# FMC_P_CAM.net
KiCad netlist of a schematic drawn in EAGLE
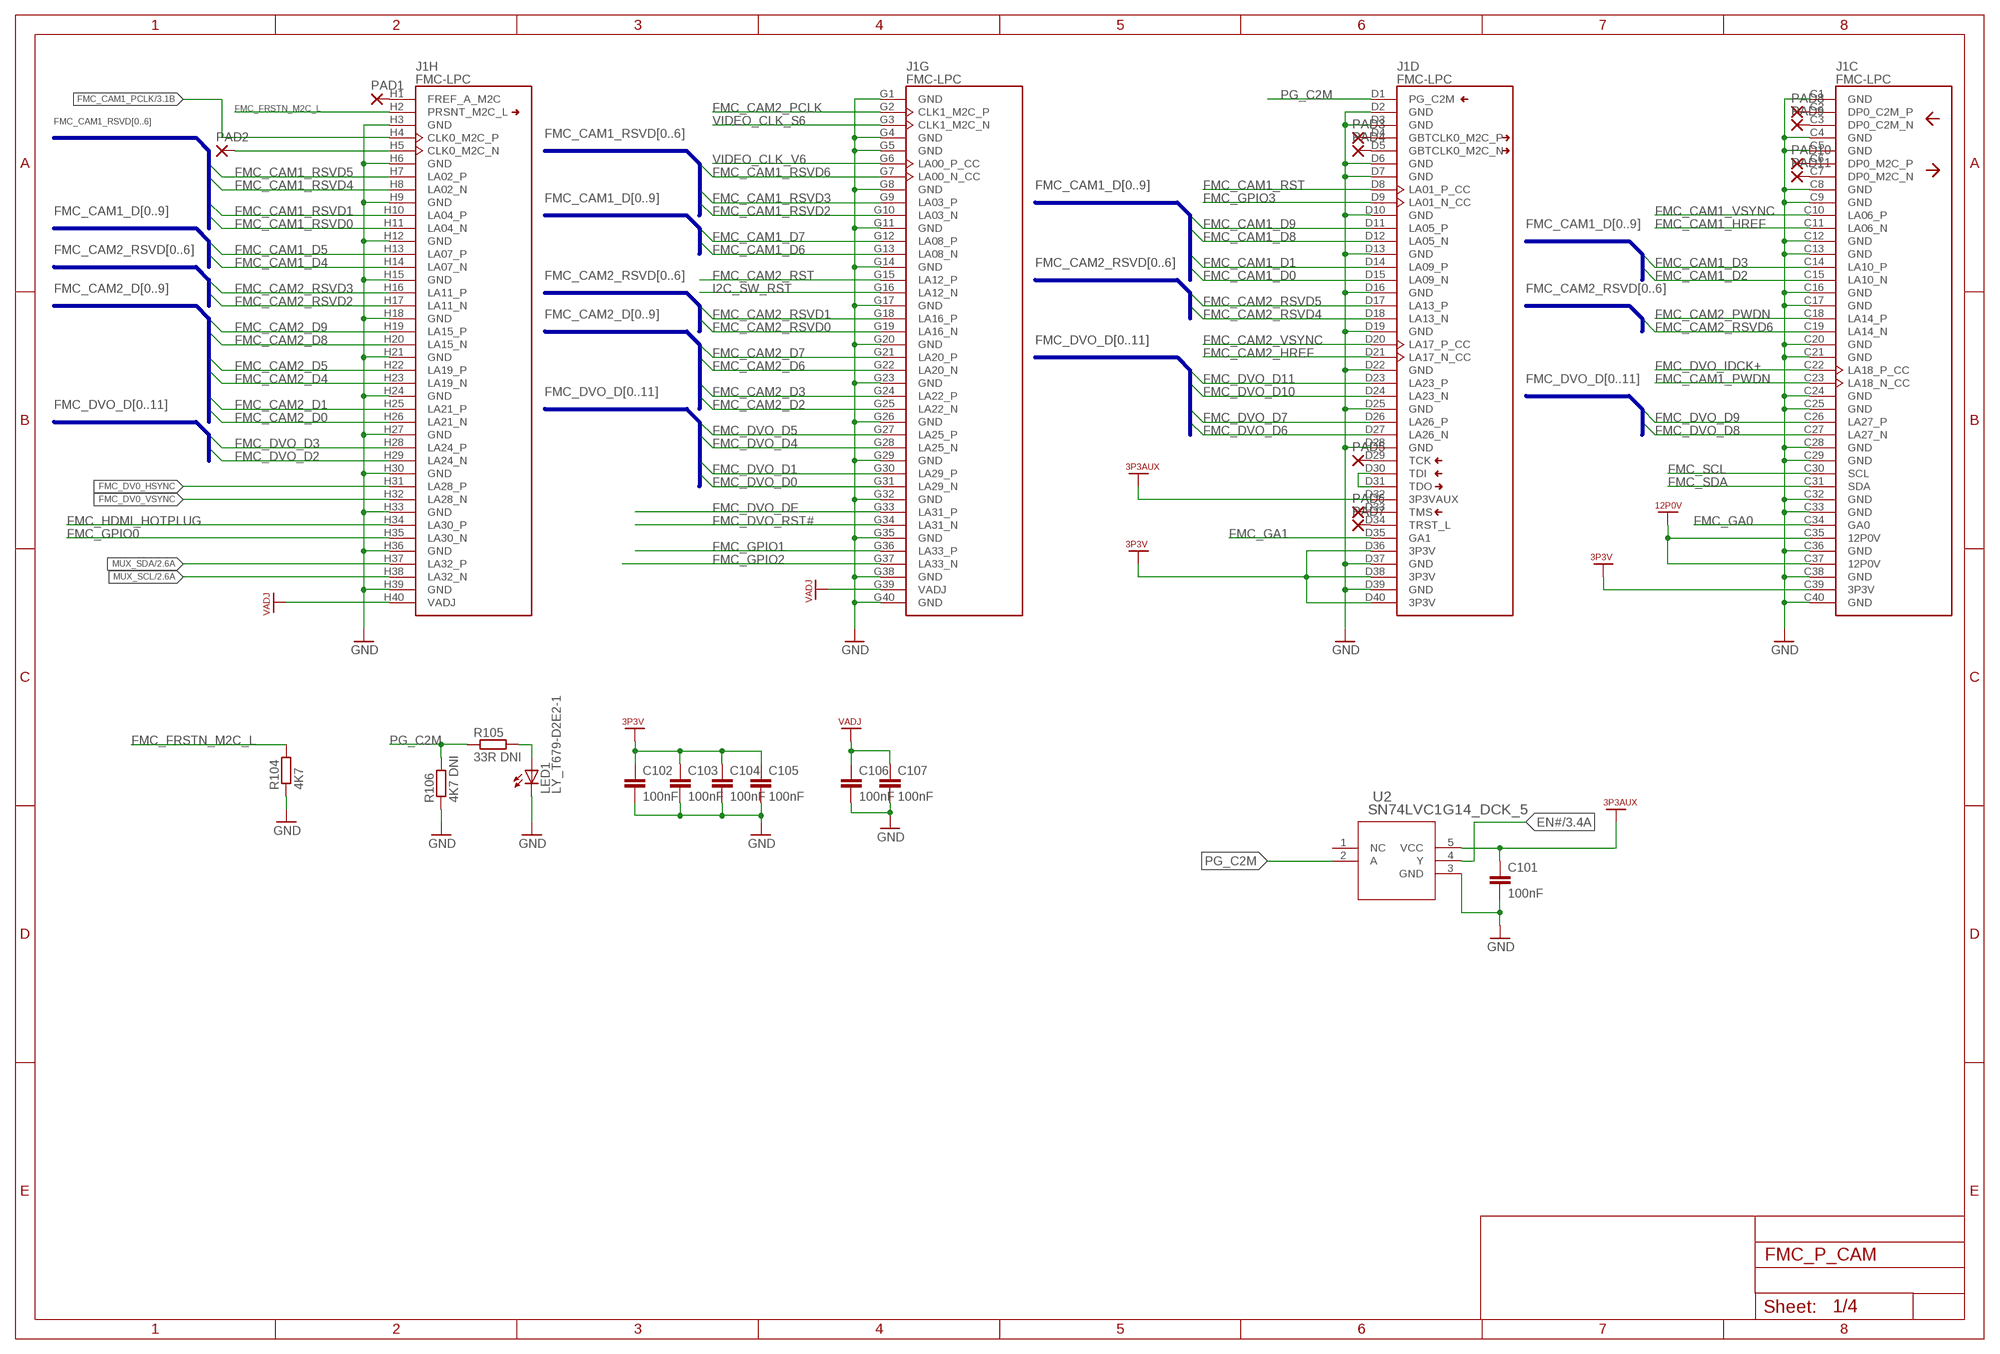
[diagram p0: schematic, sheet 1]
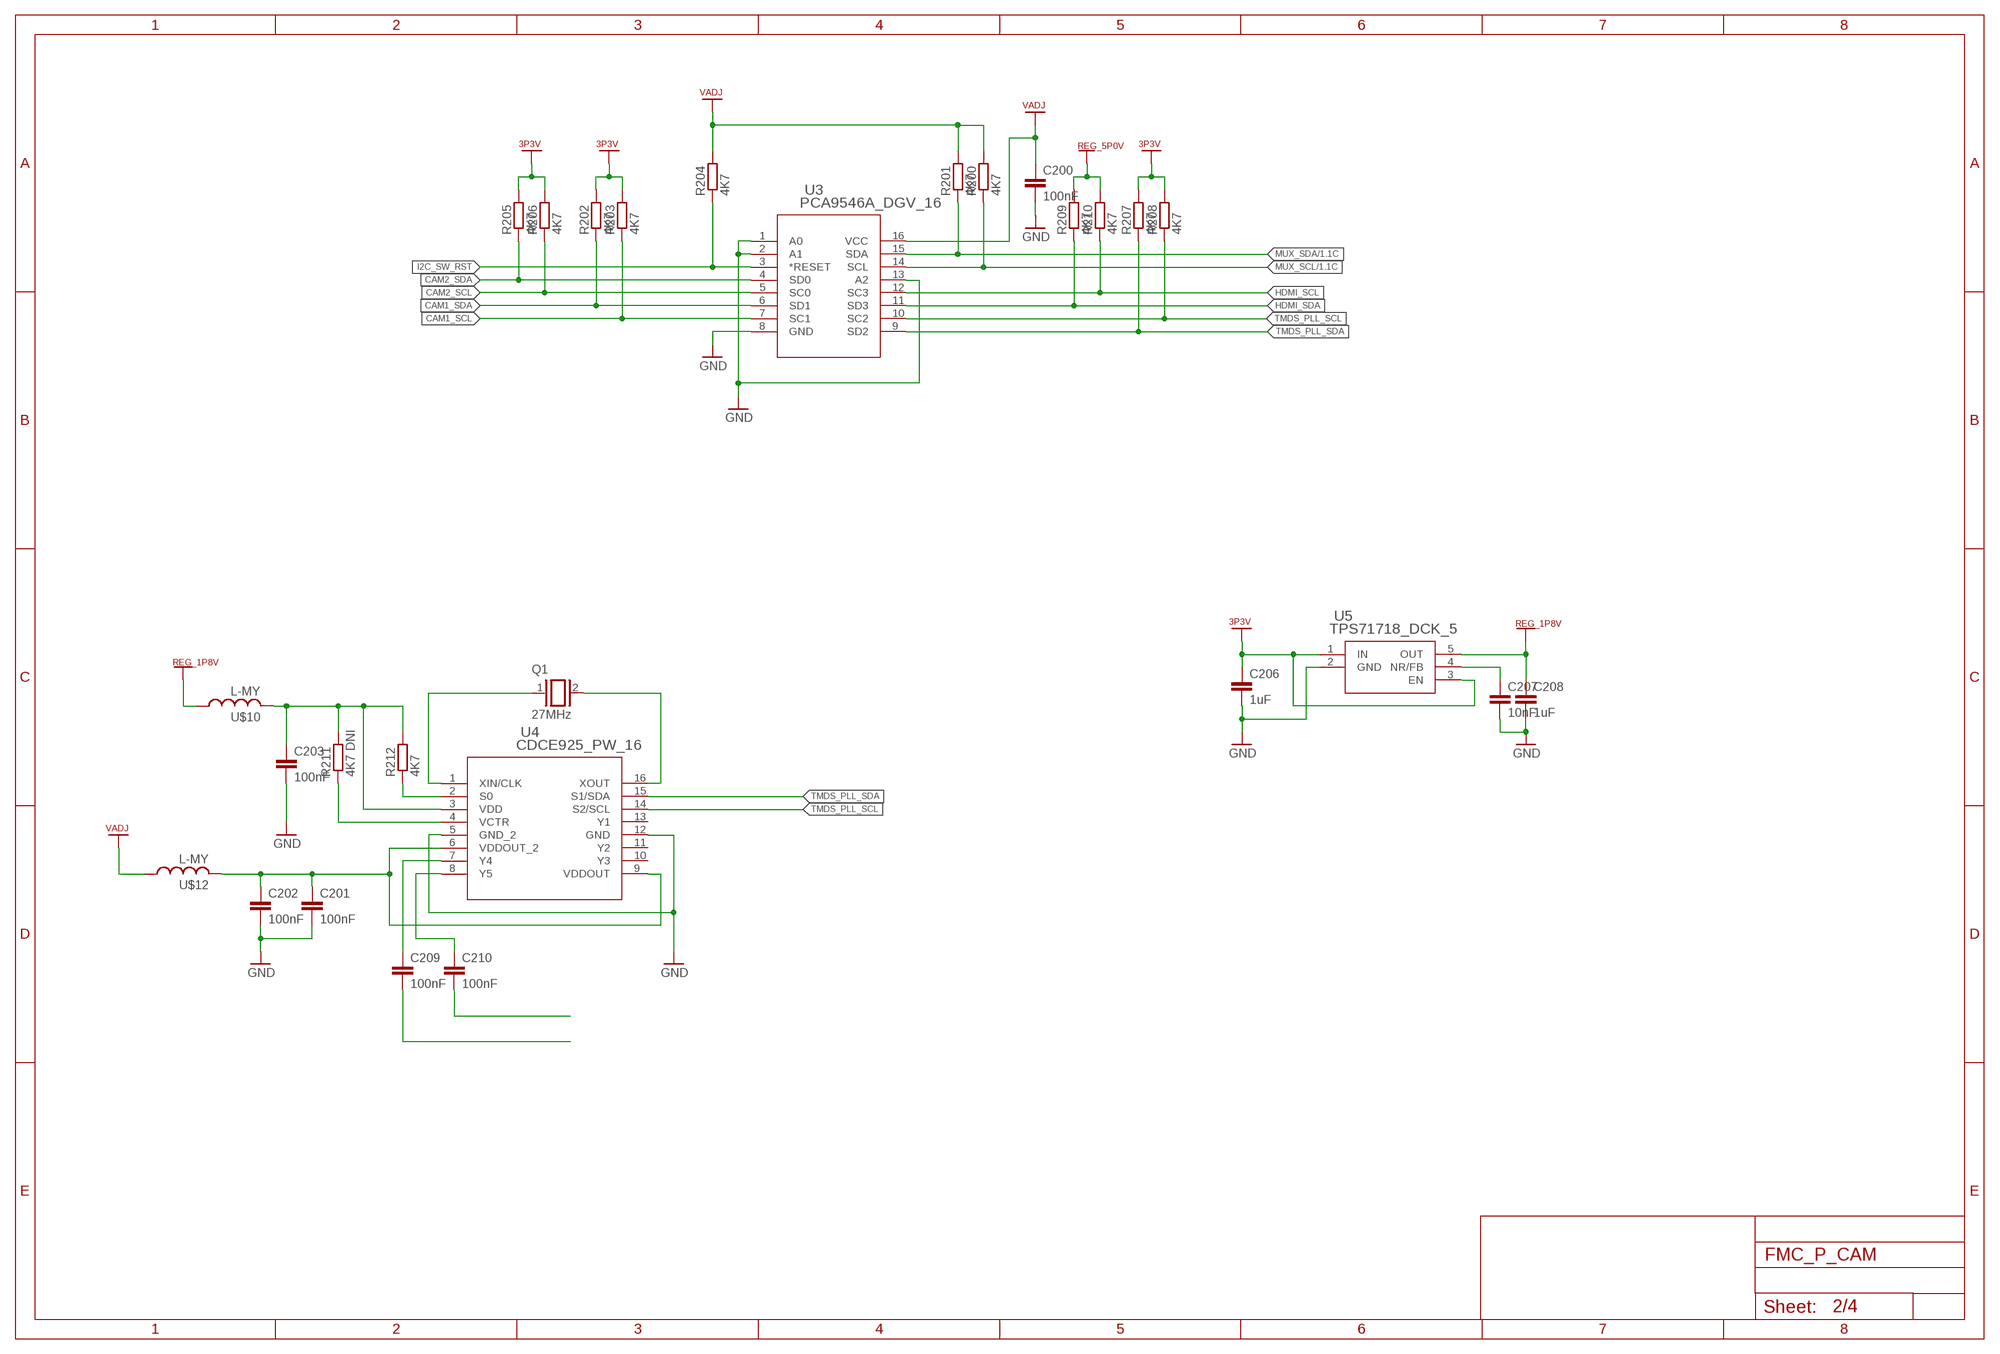
[diagram p1: schematic, sheet 2]
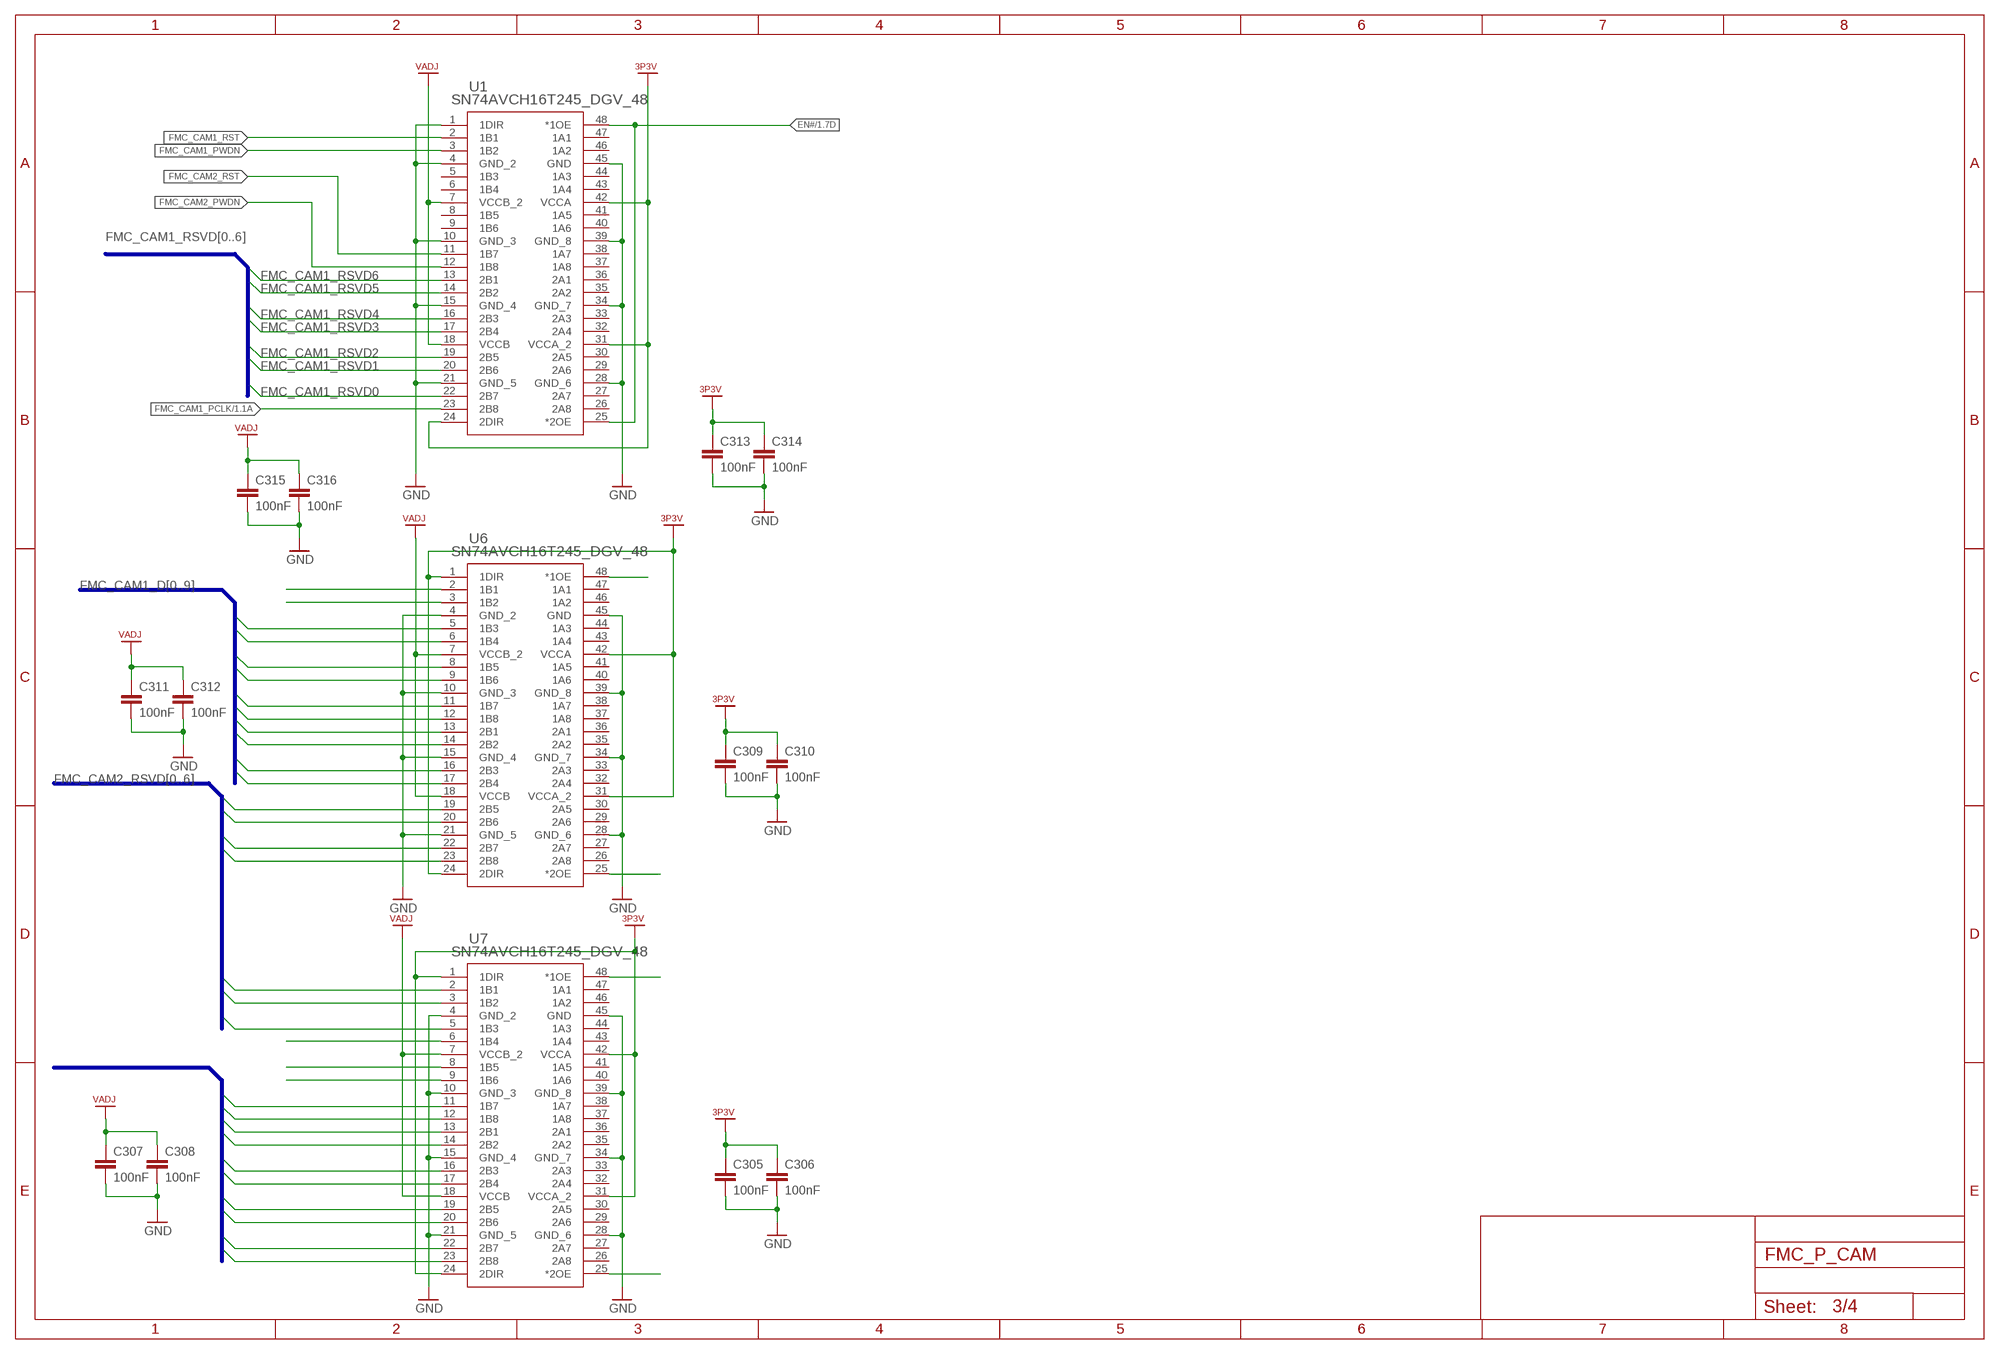
[diagram p2: schematic, sheet 3]
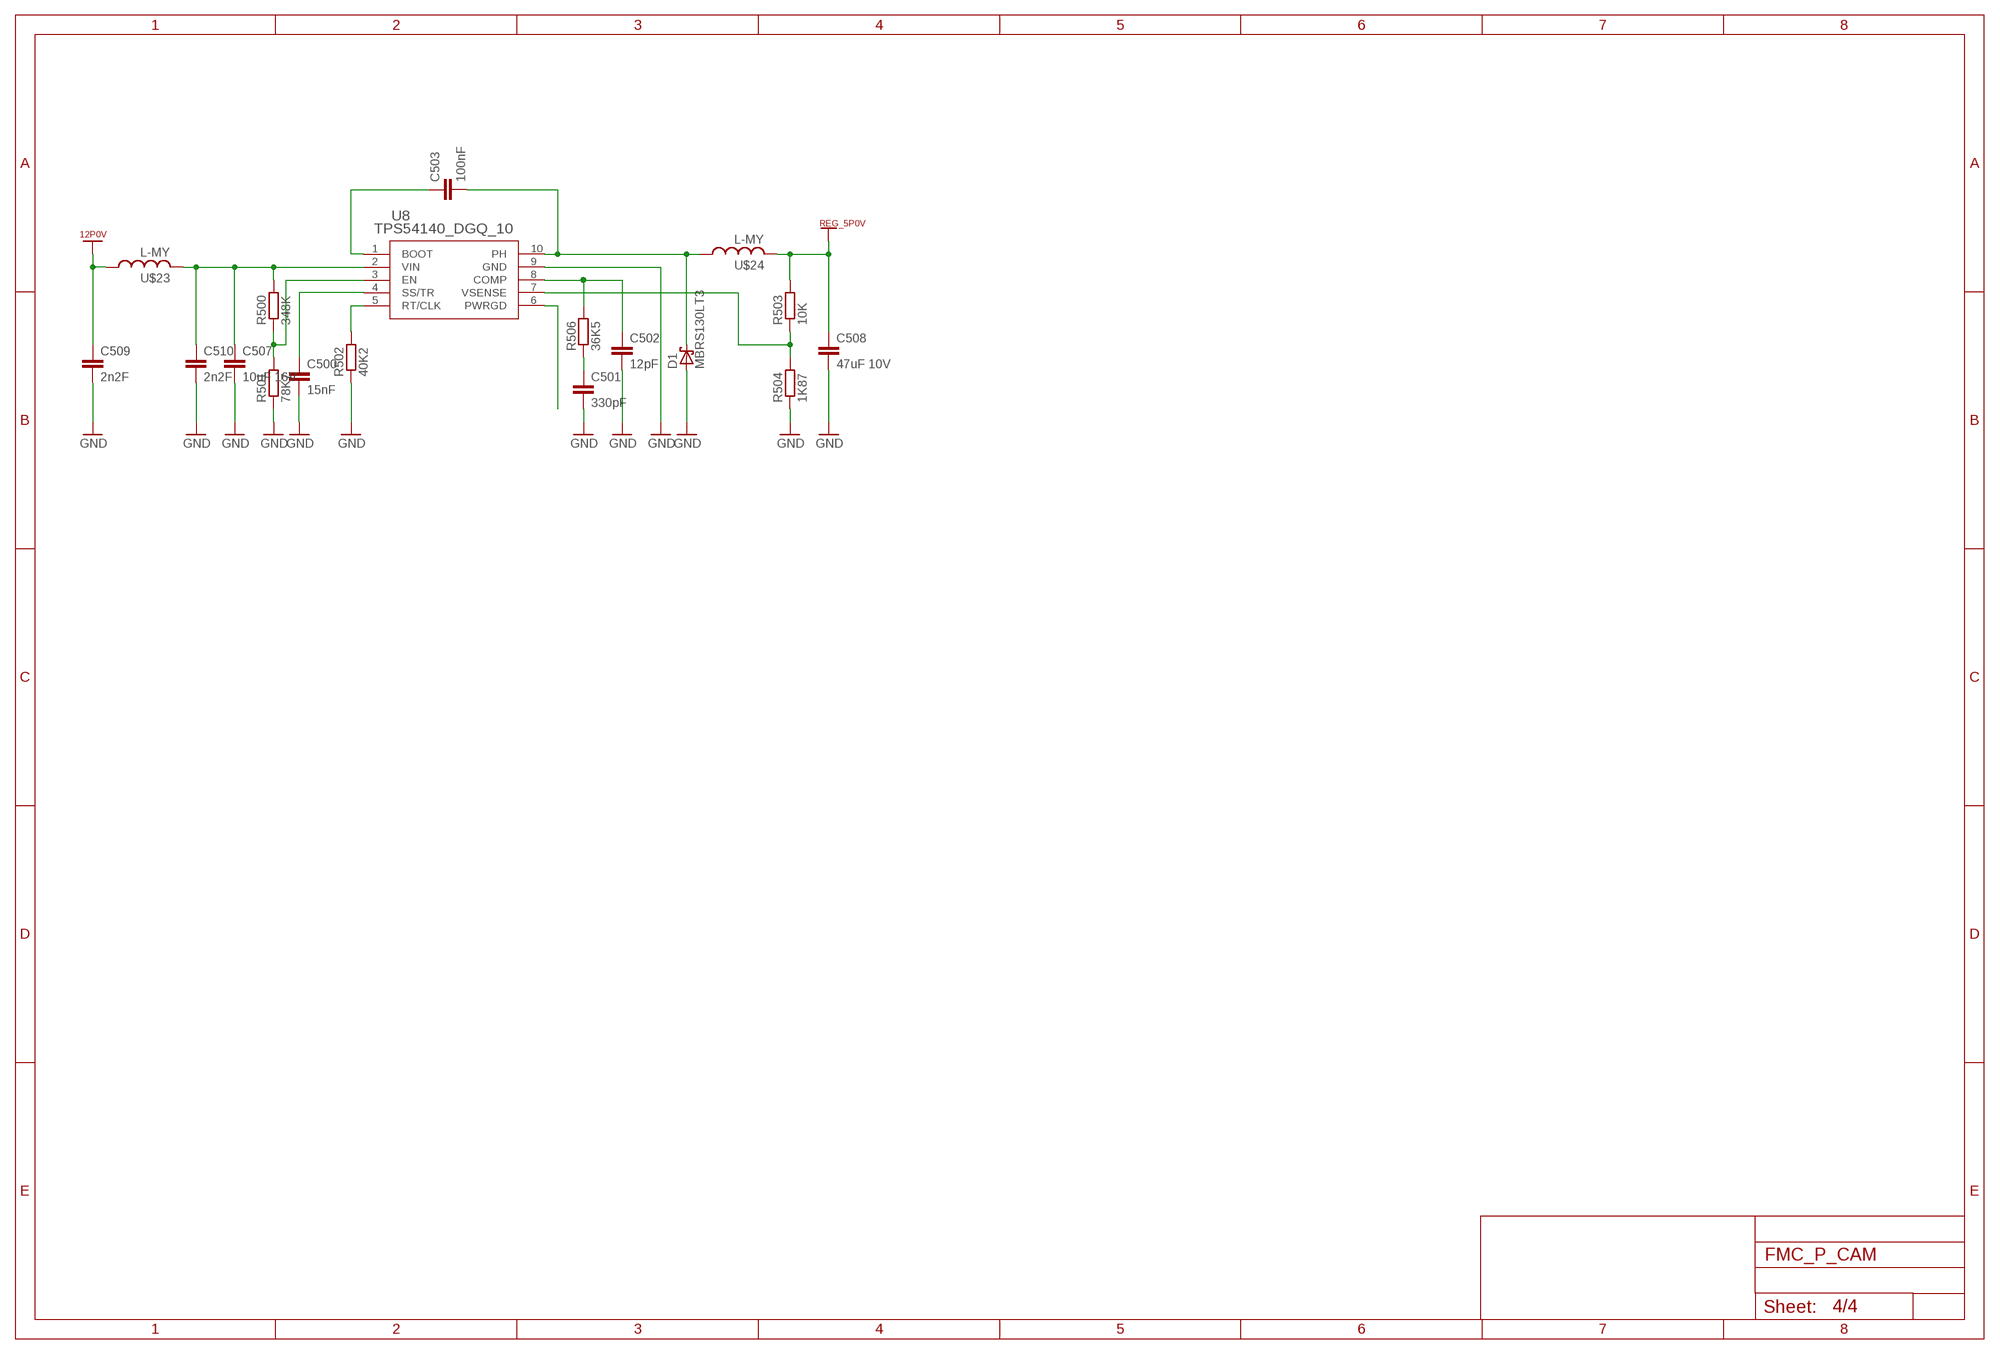
[diagram p3: schematic, sheet 4]

(export (version "E")
  (design (tool "Eeschema 10.0.6"))
  (components
    (comp (ref "C305")
      (value "100nF")
      (footprint "eagle-import:C0603")
      (libsource (lib "eagle-import") (part "rcl_C-EUC0603"))
    )
    (comp (ref "C306")
      (value "100nF")
      (footprint "eagle-import:C0603")
      (libsource (lib "eagle-import") (part "rcl_C-EUC0603"))
    )
    (comp (ref "C307")
      (value "100nF")
      (footprint "eagle-import:C0603")
      (libsource (lib "eagle-import") (part "rcl_C-EUC0603"))
    )
    (comp (ref "C308")
      (value "100nF")
      (footprint "eagle-import:C0603")
      (libsource (lib "eagle-import") (part "rcl_C-EUC0603"))
    )
    (comp (ref "C309")
      (value "100nF")
      (footprint "eagle-import:C0603")
      (libsource (lib "eagle-import") (part "rcl_C-EUC0603"))
    )
    (comp (ref "C310")
      (value "100nF")
      (footprint "eagle-import:C0603")
      (libsource (lib "eagle-import") (part "rcl_C-EUC0603"))
    )
    (comp (ref "C311")
      (value "100nF")
      (footprint "eagle-import:C0603")
      (libsource (lib "eagle-import") (part "rcl_C-EUC0603"))
    )
    (comp (ref "C312")
      (value "100nF")
      (footprint "eagle-import:C0603")
      (libsource (lib "eagle-import") (part "rcl_C-EUC0603"))
    )
    (comp (ref "C313")
      (value "100nF")
      (footprint "eagle-import:C0603")
      (libsource (lib "eagle-import") (part "rcl_C-EUC0603"))
    )
    (comp (ref "C314")
      (value "100nF")
      (footprint "eagle-import:C0603")
      (libsource (lib "eagle-import") (part "rcl_C-EUC0603"))
    )
    (comp (ref "C315")
      (value "100nF")
      (footprint "eagle-import:C0603")
      (libsource (lib "eagle-import") (part "rcl_C-EUC0603"))
    )
    (comp (ref "C316")
      (value "100nF")
      (footprint "eagle-import:C0603")
      (libsource (lib "eagle-import") (part "rcl_C-EUC0603"))
    )
    (comp (ref "U1")
      (value "SN74AVCH16T245_DGV_48")
      (footprint "eagle-import:DGV48")
      (fields
        (field (name "GENERIC_PART_NUMBER") "SN74AVCH16T245")
        (field (name "MANUFACTURER") "Texas Instruments")
        (field (name "MANUFACTURER_PART_NUMBER") "sn74avch16t245_dgv_48")
      )
      (libsource (lib "eagle-import") (part "SN74AVCH16T245_DGV_48"))
    )
    (comp (ref "U6")
      (value "SN74AVCH16T245_DGV_48")
      (footprint "eagle-import:DGV48")
      (fields
        (field (name "GENERIC_PART_NUMBER") "SN74AVCH16T245")
        (field (name "MANUFACTURER") "Texas Instruments")
        (field (name "MANUFACTURER_PART_NUMBER") "sn74avch16t245_dgv_48")
      )
      (libsource (lib "eagle-import") (part "SN74AVCH16T245_DGV_48"))
    )
    (comp (ref "U7")
      (value "SN74AVCH16T245_DGV_48")
      (footprint "eagle-import:DGV48")
      (fields
        (field (name "GENERIC_PART_NUMBER") "SN74AVCH16T245")
        (field (name "MANUFACTURER") "Texas Instruments")
        (field (name "MANUFACTURER_PART_NUMBER") "sn74avch16t245_dgv_48")
      )
      (libsource (lib "eagle-import") (part "SN74AVCH16T245_DGV_48"))
    )
    (comp (ref "C500")
      (value "15nF")
      (footprint "eagle-import:C0603")
      (libsource (lib "eagle-import") (part "rcl_C-EUC0603"))
    )
    (comp (ref "C501")
      (value "330pF")
      (footprint "eagle-import:C0603")
      (libsource (lib "eagle-import") (part "rcl_C-EUC0603"))
    )
    (comp (ref "C502")
      (value "12pF")
      (footprint "eagle-import:C0603")
      (libsource (lib "eagle-import") (part "rcl_C-EUC0603"))
    )
    (comp (ref "C503")
      (value "100nF")
      (footprint "eagle-import:C0603")
      (libsource (lib "eagle-import") (part "rcl_C-EUC0603"))
    )
    (comp (ref "C507")
      (value "10uF 16V")
      (footprint "eagle-import:C0603")
      (libsource (lib "eagle-import") (part "rcl_C-EUC0603"))
    )
    (comp (ref "C508")
      (value "47uF 10V")
      (footprint "eagle-import:C0603")
      (libsource (lib "eagle-import") (part "rcl_C-EUC0603"))
    )
    (comp (ref "C509")
      (value "2n2F")
      (footprint "eagle-import:C0603")
      (libsource (lib "eagle-import") (part "rcl_C-EUC0603"))
    )
    (comp (ref "C510")
      (value "2n2F")
      (footprint "eagle-import:C0603")
      (libsource (lib "eagle-import") (part "rcl_C-EUC0603"))
    )
    (comp (ref "D1")
      (value "MBRS130LT3")
      (footprint "eagle-import:SMB")
      (libsource (lib "eagle-import") (part "MBRS130LT3"))
    )
    (comp (ref "R500")
      (value "348K")
      (footprint "eagle-import:R0603")
      (libsource (lib "eagle-import") (part "R-EU_R0603"))
    )
    (comp (ref "R501")
      (value "78K7")
      (footprint "eagle-import:R0603")
      (libsource (lib "eagle-import") (part "R-EU_R0603"))
    )
    (comp (ref "R502")
      (value "40K2")
      (footprint "eagle-import:R0603")
      (libsource (lib "eagle-import") (part "R-EU_R0603"))
    )
    (comp (ref "R503")
      (value "10K")
      (footprint "eagle-import:R0603")
      (libsource (lib "eagle-import") (part "R-EU_R0603"))
    )
    (comp (ref "R504")
      (value "1K87")
      (footprint "eagle-import:R0603")
      (libsource (lib "eagle-import") (part "R-EU_R0603"))
    )
    (comp (ref "R506")
      (value "36K5")
      (footprint "eagle-import:R0603")
      (libsource (lib "eagle-import") (part "R-EU_R0603"))
    )
    (comp (ref "U$23")
      (value "L-MY")
      (footprint "eagle-import:R0603")
      (libsource (lib "eagle-import") (part "L-MY"))
    )
    (comp (ref "U$24")
      (value "L-MY")
      (footprint "eagle-import:R0603")
      (libsource (lib "eagle-import") (part "L-MY"))
    )
    (comp (ref "U8")
      (value "TPS54140_DGQ_10")
      (footprint "eagle-import:DGQ10_1P88X1P57")
      (fields
        (field (name "GENERIC_PART_NUMBER") "TPS54140")
        (field (name "MANUFACTURER") "Texas Instruments")
        (field (name "MANUFACTURER_PART_NUMBER") "tps54140_dgq_10")
      )
      (libsource (lib "eagle-import") (part "TPS54140_DGQ_10"))
    )
    (comp (ref "C101")
      (value "100nF")
      (footprint "eagle-import:C0603")
      (libsource (lib "eagle-import") (part "resistor_C-EUC0603"))
    )
    (comp (ref "C102")
      (value "100nF")
      (footprint "eagle-import:C0603")
      (libsource (lib "eagle-import") (part "resistor_C-EUC0603"))
    )
    (comp (ref "C103")
      (value "100nF")
      (footprint "eagle-import:C0603")
      (libsource (lib "eagle-import") (part "resistor_C-EUC0603"))
    )
    (comp (ref "C104")
      (value "100nF")
      (footprint "eagle-import:C0603")
      (libsource (lib "eagle-import") (part "resistor_C-EUC0603"))
    )
    (comp (ref "C105")
      (value "100nF")
      (footprint "eagle-import:C0603")
      (libsource (lib "eagle-import") (part "resistor_C-EUC0603"))
    )
    (comp (ref "C106")
      (value "100nF")
      (footprint "eagle-import:C0603")
      (libsource (lib "eagle-import") (part "resistor_C-EUC0603"))
    )
    (comp (ref "C107")
      (value "100nF")
      (footprint "eagle-import:C0603")
      (libsource (lib "eagle-import") (part "resistor_C-EUC0603"))
    )
    (comp (ref "J1")
      (value "FMC-LPC")
      (footprint "eagle-import:FMC-LPC-MALE")
      (fields (field (name "OC_NEWARK") "unknown"))
      (libsource (lib "eagle-import") (part "FMC-LPC"))
    )
    (comp (ref "LED1")
      (value "LY_T679-D2E2-1")
      (footprint "eagle-import:PLCC2")
      (libsource (lib "eagle-import") (part "_T679-?-1D2E2LY"))
    )
    (comp (ref "PAD1")
      (value "1,6/0,8")
      (footprint "eagle-import:1,6_0,8")
      (libsource (lib "eagle-import") (part "1,6/0,8"))
    )
    (comp (ref "PAD2")
      (value "1,6/0,8")
      (footprint "eagle-import:1,6_0,8")
      (libsource (lib "eagle-import") (part "1,6/0,8"))
    )
    (comp (ref "PAD3")
      (value "1,6/0,8")
      (footprint "eagle-import:1,6_0,8")
      (libsource (lib "eagle-import") (part "1,6/0,8"))
    )
    (comp (ref "PAD4")
      (value "1,6/0,8")
      (footprint "eagle-import:1,6_0,8")
      (libsource (lib "eagle-import") (part "1,6/0,8"))
    )
    (comp (ref "PAD5")
      (value "1,6/0,8")
      (footprint "eagle-import:1,6_0,8")
      (libsource (lib "eagle-import") (part "1,6/0,8"))
    )
    (comp (ref "PAD6")
      (value "1,6/0,8")
      (footprint "eagle-import:1,6_0,8")
      (libsource (lib "eagle-import") (part "1,6/0,8"))
    )
    (comp (ref "PAD7")
      (value "1,6/0,8")
      (footprint "eagle-import:1,6_0,8")
      (libsource (lib "eagle-import") (part "1,6/0,8"))
    )
    (comp (ref "PAD8")
      (value "1,6/0,8")
      (footprint "eagle-import:1,6_0,8")
      (libsource (lib "eagle-import") (part "1,6/0,8"))
    )
    (comp (ref "PAD9")
      (value "1,6/0,8")
      (footprint "eagle-import:1,6_0,8")
      (libsource (lib "eagle-import") (part "1,6/0,8"))
    )
    (comp (ref "PAD10")
      (value "1,6/0,8")
      (footprint "eagle-import:1,6_0,8")
      (libsource (lib "eagle-import") (part "1,6/0,8"))
    )
    (comp (ref "PAD11")
      (value "1,6/0,8")
      (footprint "eagle-import:1,6_0,8")
      (libsource (lib "eagle-import") (part "1,6/0,8"))
    )
    (comp (ref "R104")
      (value "4K7")
      (footprint "eagle-import:R0603")
      (libsource (lib "eagle-import") (part "resistor_R-EU_R0603"))
    )
    (comp (ref "R105")
      (value "33R DNI")
      (footprint "eagle-import:R0603")
      (libsource (lib "eagle-import") (part "resistor_R-EU_R0603"))
    )
    (comp (ref "R106")
      (value "4K7 DNI")
      (footprint "eagle-import:R0603")
      (libsource (lib "eagle-import") (part "resistor_R-EU_R0603"))
    )
    (comp (ref "U2")
      (value "SN74LVC1G14_DCK_5")
      (footprint "eagle-import:DCK5")
      (fields
        (field (name "GENERIC_PART_NUMBER") "SN74LVC1G14")
        (field (name "MANUFACTURER") "Texas Instruments")
        (field (name "MANUFACTURER_PART_NUMBER") "sn74lvc1g14_dck_5")
      )
      (libsource (lib "eagle-import") (part "SN74LVC1G14_DCK_5"))
    )
    (comp (ref "C200")
      (value "100nF")
      (footprint "eagle-import:C0603")
      (libsource (lib "eagle-import") (part "C-EUC0603"))
    )
    (comp (ref "C201")
      (value "100nF")
      (footprint "eagle-import:C0603")
      (libsource (lib "eagle-import") (part "C-EUC0603"))
    )
    (comp (ref "C202")
      (value "100nF")
      (footprint "eagle-import:C0603")
      (libsource (lib "eagle-import") (part "C-EUC0603"))
    )
    (comp (ref "C203")
      (value "100nF")
      (footprint "eagle-import:C0603")
      (libsource (lib "eagle-import") (part "C-EUC0603"))
    )
    (comp (ref "C206")
      (value "1uF")
      (footprint "eagle-import:C0603")
      (libsource (lib "eagle-import") (part "C-EUC0603"))
    )
    (comp (ref "C207")
      (value "10nF")
      (footprint "eagle-import:C0603")
      (libsource (lib "eagle-import") (part "C-EUC0603"))
    )
    (comp (ref "C208")
      (value "1uF")
      (footprint "eagle-import:C0603")
      (libsource (lib "eagle-import") (part "C-EUC0603"))
    )
    (comp (ref "C209")
      (value "100nF")
      (footprint "eagle-import:C0603")
      (libsource (lib "eagle-import") (part "C-EUC0603"))
    )
    (comp (ref "C210")
      (value "100nF")
      (footprint "eagle-import:C0603")
      (libsource (lib "eagle-import") (part "C-EUC0603"))
    )
    (comp (ref "Q1")
      (value "27MHz")
      (footprint "eagle-import:Q")
      (libsource (lib "eagle-import") (part "XTAL"))
    )
    (comp (ref "R200")
      (value "4K7")
      (footprint "eagle-import:R0603")
      (libsource (lib "eagle-import") (part "resistor_R-EU_R0603"))
    )
    (comp (ref "R201")
      (value "4K7")
      (footprint "eagle-import:R0603")
      (libsource (lib "eagle-import") (part "resistor_R-EU_R0603"))
    )
    (comp (ref "R202")
      (value "4K7")
      (footprint "eagle-import:R0603")
      (libsource (lib "eagle-import") (part "resistor_R-EU_R0603"))
    )
    (comp (ref "R203")
      (value "4K7")
      (footprint "eagle-import:R0603")
      (libsource (lib "eagle-import") (part "resistor_R-EU_R0603"))
    )
    (comp (ref "R204")
      (value "4K7")
      (footprint "eagle-import:R0603")
      (libsource (lib "eagle-import") (part "resistor_R-EU_R0603"))
    )
    (comp (ref "R205")
      (value "4K7")
      (footprint "eagle-import:R0603")
      (libsource (lib "eagle-import") (part "resistor_R-EU_R0603"))
    )
    (comp (ref "R206")
      (value "4K7")
      (footprint "eagle-import:R0603")
      (libsource (lib "eagle-import") (part "resistor_R-EU_R0603"))
    )
    (comp (ref "R207")
      (value "4K7")
      (footprint "eagle-import:R0603")
      (libsource (lib "eagle-import") (part "resistor_R-EU_R0603"))
    )
    (comp (ref "R208")
      (value "4K7")
      (footprint "eagle-import:R0603")
      (libsource (lib "eagle-import") (part "resistor_R-EU_R0603"))
    )
    (comp (ref "R209")
      (value "4K7")
      (footprint "eagle-import:R0603")
      (libsource (lib "eagle-import") (part "resistor_R-EU_R0603"))
    )
    (comp (ref "R210")
      (value "4K7")
      (footprint "eagle-import:R0603")
      (libsource (lib "eagle-import") (part "resistor_R-EU_R0603"))
    )
    (comp (ref "R211")
      (value "4K7 DNI")
      (footprint "eagle-import:R0603")
      (libsource (lib "eagle-import") (part "resistor_R-EU_R0603"))
    )
    (comp (ref "R212")
      (value "4K7")
      (footprint "eagle-import:R0603")
      (libsource (lib "eagle-import") (part "resistor_R-EU_R0603"))
    )
    (comp (ref "U$10")
      (value "L-MY")
      (footprint "eagle-import:R0603")
      (libsource (lib "eagle-import") (part "L-MY"))
    )
    (comp (ref "U$12")
      (value "L-MY")
      (footprint "eagle-import:R0603")
      (libsource (lib "eagle-import") (part "L-MY"))
    )
    (comp (ref "U3")
      (value "PCA9546A_DGV_16")
      (footprint "eagle-import:DGV16")
      (fields
        (field (name "GENERIC_PART_NUMBER") "PCA9546A")
        (field (name "MANUFACTURER") "Texas Instruments")
        (field (name "MANUFACTURER_PART_NUMBER") "pca9546a_dgv_16")
      )
      (libsource (lib "eagle-import") (part "PCA9546A_DGV_16"))
    )
    (comp (ref "U4")
      (value "CDCE925_PW_16")
      (footprint "eagle-import:PW16")
      (fields
        (field (name "GENERIC_PART_NUMBER") "CDCE925")
        (field (name "MANUFACTURER") "Texas Instruments")
      )
      (libsource (lib "eagle-import") (part "CDCE925_PW_16"))
    )
    (comp (ref "U5")
      (value "TPS71718_DCK_5")
      (footprint "eagle-import:DCK5")
      (fields
        (field (name "GENERIC_PART_NUMBER") "TPS71718")
        (field (name "MANUFACTURER") "Texas Instruments")
        (field (name "MANUFACTURER_PART_NUMBER") "tps71718_dck_5")
      )
      (libsource (lib "eagle-import") (part "TPS71718_DCK_5"))
    )
  )
  (nets
    (net (code "9") (name "3P3AUX") (class "Default")
      (node (ref "C101") (pin "1") (pinfunction "1_1") (pintype "passive"))
      (node (ref "J1") (pin "D32") (pinfunction "3P3VAUX_D32") (pintype "passive"))
      (node (ref "U2") (pin "5") (pinfunction "VCC_5") (pintype "power_in"))
    )
    (net (code "10") (name "3P3V") (class "Default")
      (node (ref "C102") (pin "1") (pinfunction "1_1") (pintype "passive"))
      (node (ref "C103") (pin "1") (pinfunction "1_1") (pintype "passive"))
      (node (ref "C104") (pin "1") (pinfunction "1_1") (pintype "passive"))
      (node (ref "C105") (pin "1") (pinfunction "1_1") (pintype "passive"))
      (node (ref "C206") (pin "1") (pinfunction "1_1") (pintype "passive"))
      (node (ref "C305") (pin "1") (pinfunction "1_1") (pintype "passive"))
      (node (ref "C306") (pin "1") (pinfunction "1_1") (pintype "passive"))
      (node (ref "C309") (pin "1") (pinfunction "1_1") (pintype "passive"))
      (node (ref "C310") (pin "1") (pinfunction "1_1") (pintype "passive"))
      (node (ref "C313") (pin "1") (pinfunction "1_1") (pintype "passive"))
      (node (ref "C314") (pin "1") (pinfunction "1_1") (pintype "passive"))
      (node (ref "J1") (pin "C39") (pinfunction "3P3V_C39") (pintype "passive"))
      (node (ref "J1") (pin "D36") (pinfunction "3P3V_D36") (pintype "passive"))
      (node (ref "J1") (pin "D38") (pinfunction "3P3V_D38") (pintype "passive"))
      (node (ref "J1") (pin "D40") (pinfunction "3P3V_D40") (pintype "passive"))
      (node (ref "R202") (pin "2") (pinfunction "2_2") (pintype "passive"))
      (node (ref "R203") (pin "2") (pinfunction "2_2") (pintype "passive"))
      (node (ref "R205") (pin "2") (pinfunction "2_2") (pintype "passive"))
      (node (ref "R206") (pin "2") (pinfunction "2_2") (pintype "passive"))
      (node (ref "R207") (pin "2") (pinfunction "2_2") (pintype "passive"))
      (node (ref "R208") (pin "2") (pinfunction "2_2") (pintype "passive"))
      (node (ref "U1") (pin "24") (pinfunction "2DIR_24") (pintype "input"))
      (node (ref "U1") (pin "31") (pinfunction "VCCA_2_31") (pintype "power_in"))
      (node (ref "U1") (pin "42") (pinfunction "VCCA_42") (pintype "power_in"))
      (node (ref "U5") (pin "1") (pinfunction "IN_1") (pintype "input"))
      (node (ref "U5") (pin "3") (pinfunction "EN_3") (pintype "passive"))
      (node (ref "U6") (pin "1") (pinfunction "1DIR_1") (pintype "input"))
      (node (ref "U6") (pin "24") (pinfunction "2DIR_24") (pintype "input"))
      (node (ref "U6") (pin "31") (pinfunction "VCCA_2_31") (pintype "power_in"))
      (node (ref "U6") (pin "42") (pinfunction "VCCA_42") (pintype "power_in"))
      (node (ref "U7") (pin "1") (pinfunction "1DIR_1") (pintype "input"))
      (node (ref "U7") (pin "24") (pinfunction "2DIR_24") (pintype "input"))
      (node (ref "U7") (pin "31") (pinfunction "VCCA_2_31") (pintype "power_in"))
      (node (ref "U7") (pin "42") (pinfunction "VCCA_42") (pintype "power_in"))
    )
    (net (code "11") (name "12P0V") (class "Default")
      (node (ref "C509") (pin "1") (pinfunction "1_1") (pintype "passive"))
      (node (ref "J1") (pin "C35") (pinfunction "12P0V_C35") (pintype "passive"))
      (node (ref "J1") (pin "C37") (pinfunction "12P0V_C37") (pintype "passive"))
      (node (ref "U$23") (pin "1") (pinfunction "1_1") (pintype "passive"))
    )
    (net (code "12") (name "CAM1_SCL") (class "Default")
      (node (ref "R203") (pin "1") (pinfunction "1_1") (pintype "passive"))
      (node (ref "U3") (pin "7") (pinfunction "SC1_7") (pintype "passive"))
    )
    (net (code "13") (name "CAM1_SDA") (class "Default")
      (node (ref "R202") (pin "1") (pinfunction "1_1") (pintype "passive"))
      (node (ref "U3") (pin "6") (pinfunction "SD1_6") (pintype "passive"))
    )
    (net (code "14") (name "CAM2_SCL") (class "Default")
      (node (ref "R206") (pin "1") (pinfunction "1_1") (pintype "passive"))
      (node (ref "U3") (pin "5") (pinfunction "SC0_5") (pintype "passive"))
    )
    (net (code "15") (name "CAM2_SDA") (class "Default")
      (node (ref "R205") (pin "1") (pinfunction "1_1") (pintype "passive"))
      (node (ref "U3") (pin "4") (pinfunction "SD0_4") (pintype "passive"))
    )
    (net (code "16") (name "EN#") (class "Default")
      (node (ref "U1") (pin "25") (pinfunction "*2OE_25") (pintype "input"))
      (node (ref "U1") (pin "48") (pinfunction "*1OE_48") (pintype "input"))
      (node (ref "U2") (pin "4") (pinfunction "Y_4") (pintype "output"))
      (node (ref "U6") (pin "25") (pinfunction "*2OE_25") (pintype "input"))
      (node (ref "U6") (pin "48") (pinfunction "*1OE_48") (pintype "input"))
      (node (ref "U7") (pin "25") (pinfunction "*2OE_25") (pintype "input"))
      (node (ref "U7") (pin "48") (pinfunction "*1OE_48") (pintype "input"))
    )
    (net (code "17") (name "FMC_CAM1_D0") (class "Default")
      (node (ref "J1") (pin "D15") (pinfunction "LA09_N_D15") (pintype "bidirectional"))
      (node (ref "U6") (pin "17") (pinfunction "2B4_17") (pintype "bidirectional"))
    )
    (net (code "18") (name "FMC_CAM1_D1") (class "Default")
      (node (ref "J1") (pin "D14") (pinfunction "LA09_P_D14") (pintype "bidirectional"))
      (node (ref "U6") (pin "16") (pinfunction "2B3_16") (pintype "bidirectional"))
    )
    (net (code "19") (name "FMC_CAM1_D2") (class "Default")
      (node (ref "J1") (pin "C15") (pinfunction "LA10_N_C15") (pintype "bidirectional"))
      (node (ref "U6") (pin "14") (pinfunction "2B2_14") (pintype "bidirectional"))
    )
    (net (code "20") (name "FMC_CAM1_D3") (class "Default")
      (node (ref "J1") (pin "C14") (pinfunction "LA10_P_C14") (pintype "bidirectional"))
      (node (ref "U6") (pin "13") (pinfunction "2B1_13") (pintype "bidirectional"))
    )
    (net (code "21") (name "FMC_CAM1_D4") (class "Default")
      (node (ref "J1") (pin "H14") (pinfunction "LA07_N_H14") (pintype "bidirectional"))
      (node (ref "U6") (pin "12") (pinfunction "1B8_12") (pintype "bidirectional"))
    )
    (net (code "22") (name "FMC_CAM1_D5") (class "Default")
      (node (ref "J1") (pin "H13") (pinfunction "LA07_P_H13") (pintype "bidirectional"))
      (node (ref "U6") (pin "11") (pinfunction "1B7_11") (pintype "bidirectional"))
    )
    (net (code "23") (name "FMC_CAM1_D6") (class "Default")
      (node (ref "J1") (pin "G13") (pinfunction "LA08_N_G13") (pintype "bidirectional"))
      (node (ref "U6") (pin "9") (pinfunction "1B6_9") (pintype "bidirectional"))
    )
    (net (code "24") (name "FMC_CAM1_D7") (class "Default")
      (node (ref "J1") (pin "G12") (pinfunction "LA08_P_G12") (pintype "bidirectional"))
      (node (ref "U6") (pin "8") (pinfunction "1B5_8") (pintype "bidirectional"))
    )
    (net (code "25") (name "FMC_CAM1_D8") (class "Default")
      (node (ref "J1") (pin "D12") (pinfunction "LA05_N_D12") (pintype "bidirectional"))
      (node (ref "U6") (pin "6") (pinfunction "1B4_6") (pintype "bidirectional"))
    )
    (net (code "26") (name "FMC_CAM1_D9") (class "Default")
      (node (ref "J1") (pin "D11") (pinfunction "LA05_P_D11") (pintype "bidirectional"))
      (node (ref "U6") (pin "5") (pinfunction "1B3_5") (pintype "bidirectional"))
    )
    (net (code "27") (name "FMC_CAM1_HREF") (class "Default")
      (node (ref "J1") (pin "C11") (pinfunction "LA06_N_C11") (pintype "bidirectional"))
      (node (ref "U6") (pin "3") (pinfunction "1B2_3") (pintype "bidirectional"))
    )
    (net (code "28") (name "FMC_CAM1_PCLK") (class "Default")
      (node (ref "J1") (pin "H4") (pinfunction "CLK0_M2C_P_H4") (pintype "bidirectional"))
      (node (ref "U1") (pin "23") (pinfunction "2B8_23") (pintype "bidirectional"))
    )
    (net (code "29") (name "FMC_CAM1_PWDN") (class "Default")
      (node (ref "J1") (pin "C23") (pinfunction "LA18_N_CC_C23") (pintype "bidirectional"))
      (node (ref "U1") (pin "3") (pinfunction "1B2_3") (pintype "bidirectional"))
    )
    (net (code "30") (name "FMC_CAM1_RST") (class "Default")
      (node (ref "J1") (pin "D8") (pinfunction "LA01_P_CC_D8") (pintype "bidirectional"))
      (node (ref "U1") (pin "2") (pinfunction "1B1_2") (pintype "bidirectional"))
    )
    (net (code "31") (name "FMC_CAM1_RSVD0") (class "Default")
      (node (ref "J1") (pin "H11") (pinfunction "LA04_N_H11") (pintype "bidirectional"))
      (node (ref "U1") (pin "22") (pinfunction "2B7_22") (pintype "bidirectional"))
    )
    (net (code "32") (name "FMC_CAM1_RSVD1") (class "Default")
      (node (ref "J1") (pin "H10") (pinfunction "LA04_P_H10") (pintype "bidirectional"))
      (node (ref "U1") (pin "20") (pinfunction "2B6_20") (pintype "bidirectional"))
    )
    (net (code "33") (name "FMC_CAM1_RSVD2") (class "Default")
      (node (ref "J1") (pin "G10") (pinfunction "LA03_N_G10") (pintype "bidirectional"))
      (node (ref "U1") (pin "19") (pinfunction "2B5_19") (pintype "bidirectional"))
    )
    (net (code "34") (name "FMC_CAM1_RSVD3") (class "Default")
      (node (ref "J1") (pin "G9") (pinfunction "LA03_P_G9") (pintype "bidirectional"))
      (node (ref "U1") (pin "17") (pinfunction "2B4_17") (pintype "bidirectional"))
    )
    (net (code "35") (name "FMC_CAM1_RSVD4") (class "Default")
      (node (ref "J1") (pin "H8") (pinfunction "LA02_N_H8") (pintype "bidirectional"))
      (node (ref "U1") (pin "16") (pinfunction "2B3_16") (pintype "bidirectional"))
    )
    (net (code "36") (name "FMC_CAM1_RSVD5") (class "Default")
      (node (ref "J1") (pin "H7") (pinfunction "LA02_P_H7") (pintype "bidirectional"))
      (node (ref "U1") (pin "14") (pinfunction "2B2_14") (pintype "bidirectional"))
    )
    (net (code "37") (name "FMC_CAM1_RSVD6") (class "Default")
      (node (ref "J1") (pin "G7") (pinfunction "LA00_N_CC_G7") (pintype "bidirectional"))
      (node (ref "U1") (pin "13") (pinfunction "2B1_13") (pintype "bidirectional"))
    )
    (net (code "38") (name "FMC_CAM1_VSYNC") (class "Default")
      (node (ref "J1") (pin "C10") (pinfunction "LA06_P_C10") (pintype "bidirectional"))
      (node (ref "U6") (pin "2") (pinfunction "1B1_2") (pintype "bidirectional"))
    )
    (net (code "39") (name "FMC_CAM2_D0") (class "Default")
      (node (ref "J1") (pin "H26") (pinfunction "LA21_N_H26") (pintype "bidirectional"))
      (node (ref "U7") (pin "23") (pinfunction "2B8_23") (pintype "bidirectional"))
    )
    (net (code "40") (name "FMC_CAM2_D1") (class "Default")
      (node (ref "J1") (pin "H25") (pinfunction "LA21_P_H25") (pintype "bidirectional"))
      (node (ref "U7") (pin "22") (pinfunction "2B7_22") (pintype "bidirectional"))
    )
    (net (code "41") (name "FMC_CAM2_D2") (class "Default")
      (node (ref "J1") (pin "G25") (pinfunction "LA22_N_G25") (pintype "bidirectional"))
      (node (ref "U7") (pin "20") (pinfunction "2B6_20") (pintype "bidirectional"))
    )
    (net (code "42") (name "FMC_CAM2_D3") (class "Default")
      (node (ref "J1") (pin "G24") (pinfunction "LA22_P_G24") (pintype "bidirectional"))
      (node (ref "U7") (pin "19") (pinfunction "2B5_19") (pintype "bidirectional"))
    )
    (net (code "43") (name "FMC_CAM2_D4") (class "Default")
      (node (ref "J1") (pin "H23") (pinfunction "LA19_N_H23") (pintype "bidirectional"))
      (node (ref "U7") (pin "17") (pinfunction "2B4_17") (pintype "bidirectional"))
    )
    (net (code "44") (name "FMC_CAM2_D5") (class "Default")
      (node (ref "J1") (pin "H22") (pinfunction "LA19_P_H22") (pintype "bidirectional"))
      (node (ref "U7") (pin "16") (pinfunction "2B3_16") (pintype "bidirectional"))
    )
    (net (code "45") (name "FMC_CAM2_D6") (class "Default")
      (node (ref "J1") (pin "G22") (pinfunction "LA20_N_G22") (pintype "bidirectional"))
      (node (ref "U7") (pin "14") (pinfunction "2B2_14") (pintype "bidirectional"))
    )
    (net (code "46") (name "FMC_CAM2_D7") (class "Default")
      (node (ref "J1") (pin "G21") (pinfunction "LA20_P_G21") (pintype "bidirectional"))
      (node (ref "U7") (pin "13") (pinfunction "2B1_13") (pintype "bidirectional"))
    )
    (net (code "47") (name "FMC_CAM2_D8") (class "Default")
      (node (ref "J1") (pin "H20") (pinfunction "LA15_N_H20") (pintype "bidirectional"))
      (node (ref "U7") (pin "12") (pinfunction "1B8_12") (pintype "bidirectional"))
    )
    (net (code "48") (name "FMC_CAM2_D9") (class "Default")
      (node (ref "J1") (pin "H19") (pinfunction "LA15_P_H19") (pintype "bidirectional"))
      (node (ref "U7") (pin "11") (pinfunction "1B7_11") (pintype "bidirectional"))
    )
    (net (code "49") (name "FMC_CAM2_HREF") (class "Default")
      (node (ref "J1") (pin "D21") (pinfunction "LA17_N_CC_D21") (pintype "bidirectional"))
      (node (ref "U7") (pin "9") (pinfunction "1B6_9") (pintype "bidirectional"))
    )
    (net (code "50") (name "FMC_CAM2_PCLK") (class "Default")
      (node (ref "J1") (pin "G2") (pinfunction "CLK1_M2C_P_G2") (pintype "bidirectional"))
      (node (ref "U7") (pin "6") (pinfunction "1B4_6") (pintype "bidirectional"))
    )
    (net (code "51") (name "FMC_CAM2_PWDN") (class "Default")
      (node (ref "J1") (pin "C18") (pinfunction "LA14_P_C18") (pintype "bidirectional"))
      (node (ref "U1") (pin "12") (pinfunction "1B8_12") (pintype "bidirectional"))
    )
    (net (code "52") (name "FMC_CAM2_RST") (class "Default")
      (node (ref "J1") (pin "G15") (pinfunction "LA12_P_G15") (pintype "bidirectional"))
      (node (ref "U1") (pin "11") (pinfunction "1B7_11") (pintype "bidirectional"))
    )
    (net (code "53") (name "FMC_CAM2_RSVD0") (class "Default")
      (node (ref "J1") (pin "G19") (pinfunction "LA16_N_G19") (pintype "bidirectional"))
      (node (ref "U7") (pin "5") (pinfunction "1B3_5") (pintype "bidirectional"))
    )
    (net (code "54") (name "FMC_CAM2_RSVD1") (class "Default")
      (node (ref "J1") (pin "G18") (pinfunction "LA16_P_G18") (pintype "bidirectional"))
      (node (ref "U7") (pin "3") (pinfunction "1B2_3") (pintype "bidirectional"))
    )
    (net (code "55") (name "FMC_CAM2_RSVD2") (class "Default")
      (node (ref "J1") (pin "H17") (pinfunction "LA11_N_H17") (pintype "bidirectional"))
      (node (ref "U7") (pin "2") (pinfunction "1B1_2") (pintype "bidirectional"))
    )
    (net (code "56") (name "FMC_CAM2_RSVD3") (class "Default")
      (node (ref "J1") (pin "H16") (pinfunction "LA11_P_H16") (pintype "bidirectional"))
      (node (ref "U6") (pin "23") (pinfunction "2B8_23") (pintype "bidirectional"))
    )
    (net (code "57") (name "FMC_CAM2_RSVD4") (class "Default")
      (node (ref "J1") (pin "D18") (pinfunction "LA13_N_D18") (pintype "bidirectional"))
      (node (ref "U6") (pin "22") (pinfunction "2B7_22") (pintype "bidirectional"))
    )
    (net (code "58") (name "FMC_CAM2_RSVD5") (class "Default")
      (node (ref "J1") (pin "D17") (pinfunction "LA13_P_D17") (pintype "bidirectional"))
      (node (ref "U6") (pin "20") (pinfunction "2B6_20") (pintype "bidirectional"))
    )
    (net (code "59") (name "FMC_CAM2_RSVD6") (class "Default")
      (node (ref "J1") (pin "C19") (pinfunction "LA14_N_C19") (pintype "bidirectional"))
      (node (ref "U6") (pin "19") (pinfunction "2B5_19") (pintype "bidirectional"))
    )
    (net (code "60") (name "FMC_CAM2_VSYNC") (class "Default")
      (node (ref "J1") (pin "D20") (pinfunction "LA17_P_CC_D20") (pintype "bidirectional"))
      (node (ref "U7") (pin "8") (pinfunction "1B5_8") (pintype "bidirectional"))
    )
    (net (code "61") (name "FMC_DV0_HSYNC") (class "Default")
      (node (ref "J1") (pin "H31") (pinfunction "LA28_P_H31") (pintype "bidirectional"))
    )
    (net (code "62") (name "FMC_DV0_VSYNC") (class "Default")
      (node (ref "J1") (pin "H32") (pinfunction "LA28_N_H32") (pintype "bidirectional"))
    )
    (net (code "63") (name "FMC_DVO_D0") (class "Default")
      (node (ref "J1") (pin "G31") (pinfunction "LA29_N_G31") (pintype "bidirectional"))
    )
    (net (code "64") (name "FMC_DVO_D1") (class "Default")
      (node (ref "J1") (pin "G30") (pinfunction "LA29_P_G30") (pintype "bidirectional"))
    )
    (net (code "65") (name "FMC_DVO_D2") (class "Default")
      (node (ref "J1") (pin "H29") (pinfunction "LA24_N_H29") (pintype "bidirectional"))
    )
    (net (code "66") (name "FMC_DVO_D3") (class "Default")
      (node (ref "J1") (pin "H28") (pinfunction "LA24_P_H28") (pintype "bidirectional"))
    )
    (net (code "67") (name "FMC_DVO_D4") (class "Default")
      (node (ref "J1") (pin "G28") (pinfunction "LA25_N_G28") (pintype "bidirectional"))
    )
    (net (code "68") (name "FMC_DVO_D5") (class "Default")
      (node (ref "J1") (pin "G27") (pinfunction "LA25_P_G27") (pintype "bidirectional"))
    )
    (net (code "69") (name "FMC_DVO_D6") (class "Default")
      (node (ref "J1") (pin "D27") (pinfunction "LA26_N_D27") (pintype "bidirectional"))
    )
    (net (code "70") (name "FMC_DVO_D7") (class "Default")
      (node (ref "J1") (pin "D26") (pinfunction "LA26_P_D26") (pintype "bidirectional"))
    )
    (net (code "71") (name "FMC_DVO_D8") (class "Default")
      (node (ref "J1") (pin "C27") (pinfunction "LA27_N_C27") (pintype "bidirectional"))
    )
    (net (code "72") (name "FMC_DVO_D9") (class "Default")
      (node (ref "J1") (pin "C26") (pinfunction "LA27_P_C26") (pintype "bidirectional"))
    )
    (net (code "73") (name "FMC_DVO_D10") (class "Default")
      (node (ref "J1") (pin "D24") (pinfunction "LA23_N_D24") (pintype "bidirectional"))
    )
    (net (code "74") (name "FMC_DVO_D11") (class "Default")
      (node (ref "J1") (pin "D23") (pinfunction "LA23_P_D23") (pintype "bidirectional"))
    )
    (net (code "75") (name "FMC_DVO_DE") (class "Default")
      (node (ref "J1") (pin "G33") (pinfunction "LA31_P_G33") (pintype "bidirectional"))
    )
    (net (code "76") (name "FMC_DVO_IDCK+") (class "Default")
      (node (ref "J1") (pin "C22") (pinfunction "LA18_P_CC_C22") (pintype "bidirectional"))
    )
    (net (code "77") (name "FMC_DVO_RST#") (class "Default")
      (node (ref "J1") (pin "G34") (pinfunction "LA31_N_G34") (pintype "bidirectional"))
    )
    (net (code "78") (name "FMC_FRSTN_M2C_L") (class "Default")
      (node (ref "J1") (pin "H2") (pinfunction "PRSNT_M2C_L_H2") (pintype "input"))
      (node (ref "R104") (pin "2") (pinfunction "2_2") (pintype "passive"))
    )
    (net (code "79") (name "FMC_GA0") (class "Default")
      (node (ref "J1") (pin "C34") (pinfunction "GA0_C34") (pintype "output"))
    )
    (net (code "80") (name "FMC_GA1") (class "Default")
      (node (ref "J1") (pin "D35") (pinfunction "GA1_D35") (pintype "output"))
    )
    (net (code "81") (name "FMC_GPIO0") (class "Default")
      (node (ref "J1") (pin "H35") (pinfunction "LA30_N_H35") (pintype "bidirectional"))
    )
    (net (code "82") (name "FMC_GPIO1") (class "Default")
      (node (ref "J1") (pin "G36") (pinfunction "LA33_P_G36") (pintype "bidirectional"))
    )
    (net (code "83") (name "FMC_GPIO2") (class "Default")
      (node (ref "J1") (pin "G37") (pinfunction "LA33_N_G37") (pintype "bidirectional"))
    )
    (net (code "84") (name "FMC_GPIO3") (class "Default")
      (node (ref "J1") (pin "D9") (pinfunction "LA01_N_CC_D9") (pintype "bidirectional"))
    )
    (net (code "85") (name "FMC_HDMI_HOTPLUG") (class "Default")
      (node (ref "J1") (pin "H34") (pinfunction "LA30_P_H34") (pintype "bidirectional"))
    )
    (net (code "86") (name "FMC_SCL") (class "Default")
      (node (ref "J1") (pin "C30") (pinfunction "SCL_C30") (pintype "bidirectional"))
    )
    (net (code "87") (name "FMC_SDA") (class "Default")
      (node (ref "J1") (pin "C31") (pinfunction "SDA_C31") (pintype "bidirectional"))
    )
    (net (code "88") (name "GND") (class "Default")
      (node (ref "C101") (pin "2") (pinfunction "2_2") (pintype "passive"))
      (node (ref "C102") (pin "2") (pinfunction "2_2") (pintype "passive"))
      (node (ref "C103") (pin "2") (pinfunction "2_2") (pintype "passive"))
      (node (ref "C104") (pin "2") (pinfunction "2_2") (pintype "passive"))
      (node (ref "C105") (pin "2") (pinfunction "2_2") (pintype "passive"))
      (node (ref "C106") (pin "2") (pinfunction "2_2") (pintype "passive"))
      (node (ref "C107") (pin "2") (pinfunction "2_2") (pintype "passive"))
      (node (ref "C200") (pin "2") (pinfunction "2_2") (pintype "passive"))
      (node (ref "C201") (pin "2") (pinfunction "2_2") (pintype "passive"))
      (node (ref "C202") (pin "2") (pinfunction "2_2") (pintype "passive"))
      (node (ref "C203") (pin "2") (pinfunction "2_2") (pintype "passive"))
      (node (ref "C206") (pin "2") (pinfunction "2_2") (pintype "passive"))
      (node (ref "C207") (pin "2") (pinfunction "2_2") (pintype "passive"))
      (node (ref "C208") (pin "2") (pinfunction "2_2") (pintype "passive"))
      (node (ref "C305") (pin "2") (pinfunction "2_2") (pintype "passive"))
      (node (ref "C306") (pin "2") (pinfunction "2_2") (pintype "passive"))
      (node (ref "C307") (pin "2") (pinfunction "2_2") (pintype "passive"))
      (node (ref "C308") (pin "2") (pinfunction "2_2") (pintype "passive"))
      (node (ref "C309") (pin "2") (pinfunction "2_2") (pintype "passive"))
      (node (ref "C310") (pin "2") (pinfunction "2_2") (pintype "passive"))
      (node (ref "C311") (pin "2") (pinfunction "2_2") (pintype "passive"))
      (node (ref "C312") (pin "2") (pinfunction "2_2") (pintype "passive"))
      (node (ref "C313") (pin "2") (pinfunction "2_2") (pintype "passive"))
      (node (ref "C314") (pin "2") (pinfunction "2_2") (pintype "passive"))
      (node (ref "C315") (pin "2") (pinfunction "2_2") (pintype "passive"))
      (node (ref "C316") (pin "2") (pinfunction "2_2") (pintype "passive"))
      (node (ref "C500") (pin "2") (pinfunction "2_2") (pintype "passive"))
      (node (ref "C501") (pin "2") (pinfunction "2_2") (pintype "passive"))
      (node (ref "C502") (pin "2") (pinfunction "2_2") (pintype "passive"))
      (node (ref "C507") (pin "2") (pinfunction "2_2") (pintype "passive"))
      (node (ref "C508") (pin "2") (pinfunction "2_2") (pintype "passive"))
      (node (ref "C509") (pin "2") (pinfunction "2_2") (pintype "passive"))
      (node (ref "C510") (pin "2") (pinfunction "2_2") (pintype "passive"))
      (node (ref "D1") (pin "A") (pinfunction "A_A") (pintype "passive"))
      (node (ref "J1") (pin "C1") (pinfunction "GND_C1") (pintype "passive"))
      (node (ref "J1") (pin "C12") (pinfunction "GND_C12") (pintype "passive"))
      (node (ref "J1") (pin "C13") (pinfunction "GND_C13") (pintype "passive"))
      (node (ref "J1") (pin "C16") (pinfunction "GND_C16") (pintype "passive"))
      (node (ref "J1") (pin "C17") (pinfunction "GND_C17") (pintype "passive"))
      (node (ref "J1") (pin "C20") (pinfunction "GND_C20") (pintype "passive"))
      (node (ref "J1") (pin "C21") (pinfunction "GND_C21") (pintype "passive"))
      (node (ref "J1") (pin "C24") (pinfunction "GND_C24") (pintype "passive"))
      (node (ref "J1") (pin "C25") (pinfunction "GND_C25") (pintype "passive"))
      (node (ref "J1") (pin "C28") (pinfunction "GND_C28") (pintype "passive"))
      (node (ref "J1") (pin "C29") (pinfunction "GND_C29") (pintype "passive"))
      (node (ref "J1") (pin "C32") (pinfunction "GND_C32") (pintype "passive"))
      (node (ref "J1") (pin "C33") (pinfunction "GND_C33") (pintype "passive"))
      (node (ref "J1") (pin "C36") (pinfunction "GND_C36") (pintype "passive"))
      (node (ref "J1") (pin "C38") (pinfunction "GND_C38") (pintype "passive"))
      (node (ref "J1") (pin "C4") (pinfunction "GND_C4") (pintype "passive"))
      (node (ref "J1") (pin "C40") (pinfunction "GND_C40") (pintype "passive"))
      (node (ref "J1") (pin "C5") (pinfunction "GND_C5") (pintype "passive"))
      (node (ref "J1") (pin "C8") (pinfunction "GND_C8") (pintype "passive"))
      (node (ref "J1") (pin "C9") (pinfunction "GND_C9") (pintype "passive"))
      (node (ref "J1") (pin "D10") (pinfunction "GND_D10") (pintype "passive"))
      (node (ref "J1") (pin "D13") (pinfunction "GND_D13") (pintype "passive"))
      (node (ref "J1") (pin "D16") (pinfunction "GND_D16") (pintype "passive"))
      (node (ref "J1") (pin "D19") (pinfunction "GND_D19") (pintype "passive"))
      (node (ref "J1") (pin "D2") (pinfunction "GND_D2") (pintype "passive"))
      (node (ref "J1") (pin "D22") (pinfunction "GND_D22") (pintype "passive"))
      (node (ref "J1") (pin "D25") (pinfunction "GND_D25") (pintype "passive"))
      (node (ref "J1") (pin "D28") (pinfunction "GND_D28") (pintype "passive"))
      (node (ref "J1") (pin "D3") (pinfunction "GND_D3") (pintype "passive"))
      (node (ref "J1") (pin "D37") (pinfunction "GND_D37") (pintype "passive"))
      (node (ref "J1") (pin "D39") (pinfunction "GND_D39") (pintype "passive"))
      (node (ref "J1") (pin "D6") (pinfunction "GND_D6") (pintype "passive"))
      (node (ref "J1") (pin "D7") (pinfunction "GND_D7") (pintype "passive"))
      (node (ref "J1") (pin "G1") (pinfunction "GND_G1") (pintype "passive"))
      (node (ref "J1") (pin "G11") (pinfunction "GND_G11") (pintype "passive"))
      (node (ref "J1") (pin "G14") (pinfunction "GND_G14") (pintype "passive"))
      (node (ref "J1") (pin "G17") (pinfunction "GND_G17") (pintype "passive"))
      (node (ref "J1") (pin "G20") (pinfunction "GND_G20") (pintype "passive"))
      (node (ref "J1") (pin "G23") (pinfunction "GND_G23") (pintype "passive"))
      (node (ref "J1") (pin "G26") (pinfunction "GND_G26") (pintype "passive"))
      (node (ref "J1") (pin "G29") (pinfunction "GND_G29") (pintype "passive"))
      (node (ref "J1") (pin "G32") (pinfunction "GND_G32") (pintype "passive"))
      (node (ref "J1") (pin "G35") (pinfunction "GND_G35") (pintype "passive"))
      (node (ref "J1") (pin "G38") (pinfunction "GND_G38") (pintype "passive"))
      (node (ref "J1") (pin "G4") (pinfunction "GND_G4") (pintype "passive"))
      (node (ref "J1") (pin "G40") (pinfunction "GND_G40") (pintype "passive"))
      (node (ref "J1") (pin "G5") (pinfunction "GND_G5") (pintype "passive"))
      (node (ref "J1") (pin "G8") (pinfunction "GND_G8") (pintype "passive"))
      (node (ref "J1") (pin "H12") (pinfunction "GND_H12") (pintype "passive"))
      (node (ref "J1") (pin "H15") (pinfunction "GND_H15") (pintype "passive"))
      (node (ref "J1") (pin "H18") (pinfunction "GND_H18") (pintype "passive"))
      (node (ref "J1") (pin "H21") (pinfunction "GND_H21") (pintype "passive"))
      (node (ref "J1") (pin "H24") (pinfunction "GND_H24") (pintype "passive"))
      (node (ref "J1") (pin "H27") (pinfunction "GND_H27") (pintype "passive"))
      (node (ref "J1") (pin "H3") (pinfunction "GND_H3") (pintype "passive"))
      (node (ref "J1") (pin "H30") (pinfunction "GND_H30") (pintype "passive"))
      (node (ref "J1") (pin "H33") (pinfunction "GND_H33") (pintype "passive"))
      (node (ref "J1") (pin "H36") (pinfunction "GND_H36") (pintype "passive"))
      (node (ref "J1") (pin "H39") (pinfunction "GND_H39") (pintype "passive"))
      (node (ref "J1") (pin "H6") (pinfunction "GND_H6") (pintype "passive"))
      (node (ref "J1") (pin "H9") (pinfunction "GND_H9") (pintype "passive"))
      (node (ref "LED1") (pin "C") (pinfunction "C_C") (pintype "passive"))
      (node (ref "R104") (pin "1") (pinfunction "1_1") (pintype "passive"))
      (node (ref "R106") (pin "1") (pinfunction "1_1") (pintype "passive"))
      (node (ref "R501") (pin "1") (pinfunction "1_1") (pintype "passive"))
      (node (ref "R502") (pin "1") (pinfunction "1_1") (pintype "passive"))
      (node (ref "R504") (pin "1") (pinfunction "1_1") (pintype "passive"))
      (node (ref "U1") (pin "1") (pinfunction "1DIR_1") (pintype "input"))
      (node (ref "U1") (pin "10") (pinfunction "GND_3_10") (pintype "power_in"))
      (node (ref "U1") (pin "15") (pinfunction "GND_4_15") (pintype "power_in"))
      (node (ref "U1") (pin "21") (pinfunction "GND_5_21") (pintype "power_in"))
      (node (ref "U1") (pin "28") (pinfunction "GND_6_28") (pintype "power_in"))
      (node (ref "U1") (pin "34") (pinfunction "GND_7_34") (pintype "power_in"))
      (node (ref "U1") (pin "39") (pinfunction "GND_8_39") (pintype "power_in"))
      (node (ref "U1") (pin "4") (pinfunction "GND_2_4") (pintype "power_in"))
      (node (ref "U1") (pin "45") (pinfunction "GND_45") (pintype "power_in"))
      (node (ref "U2") (pin "3") (pinfunction "GND_3") (pintype "power_in"))
      (node (ref "U3") (pin "1") (pinfunction "A0_1") (pintype "input"))
      (node (ref "U3") (pin "13") (pinfunction "A2_13") (pintype "input"))
      (node (ref "U3") (pin "2") (pinfunction "A1_2") (pintype "input"))
      (node (ref "U3") (pin "8") (pinfunction "GND_8") (pintype "power_in"))
      (node (ref "U4") (pin "12") (pinfunction "GND_12") (pintype "power_in"))
      (node (ref "U4") (pin "5") (pinfunction "GND_2_5") (pintype "power_in"))
      (node (ref "U5") (pin "2") (pinfunction "GND_2") (pintype "power_in"))
      (node (ref "U6") (pin "10") (pinfunction "GND_3_10") (pintype "power_in"))
      (node (ref "U6") (pin "15") (pinfunction "GND_4_15") (pintype "power_in"))
      (node (ref "U6") (pin "21") (pinfunction "GND_5_21") (pintype "power_in"))
      (node (ref "U6") (pin "28") (pinfunction "GND_6_28") (pintype "power_in"))
      (node (ref "U6") (pin "34") (pinfunction "GND_7_34") (pintype "power_in"))
      (node (ref "U6") (pin "39") (pinfunction "GND_8_39") (pintype "power_in"))
      (node (ref "U6") (pin "4") (pinfunction "GND_2_4") (pintype "power_in"))
      (node (ref "U6") (pin "45") (pinfunction "GND_45") (pintype "power_in"))
      (node (ref "U7") (pin "10") (pinfunction "GND_3_10") (pintype "power_in"))
      (node (ref "U7") (pin "15") (pinfunction "GND_4_15") (pintype "power_in"))
      (node (ref "U7") (pin "21") (pinfunction "GND_5_21") (pintype "power_in"))
      (node (ref "U7") (pin "28") (pinfunction "GND_6_28") (pintype "power_in"))
      (node (ref "U7") (pin "34") (pinfunction "GND_7_34") (pintype "power_in"))
      (node (ref "U7") (pin "39") (pinfunction "GND_8_39") (pintype "power_in"))
      (node (ref "U7") (pin "4") (pinfunction "GND_2_4") (pintype "power_in"))
      (node (ref "U7") (pin "45") (pinfunction "GND_45") (pintype "power_in"))
      (node (ref "U8") (pin "9") (pinfunction "GND_9") (pintype "power_in"))
    )
    (net (code "89") (name "HDMI_SCL") (class "Default")
      (node (ref "R210") (pin "1") (pinfunction "1_1") (pintype "passive"))
      (node (ref "U3") (pin "12") (pinfunction "SC3_12") (pintype "passive"))
    )
    (net (code "90") (name "HDMI_SDA") (class "Default")
      (node (ref "R209") (pin "1") (pinfunction "1_1") (pintype "passive"))
      (node (ref "U3") (pin "11") (pinfunction "SD3_11") (pintype "passive"))
    )
    (net (code "91") (name "I2C_SW_RST") (class "Default")
      (node (ref "J1") (pin "G16") (pinfunction "LA12_N_G16") (pintype "bidirectional"))
      (node (ref "R204") (pin "1") (pinfunction "1_1") (pintype "passive"))
      (node (ref "U3") (pin "3") (pinfunction "*RESET_3") (pintype "input"))
    )
    (net (code "92") (name "MUX_SCL") (class "Default")
      (node (ref "J1") (pin "H38") (pinfunction "LA32_N_H38") (pintype "bidirectional"))
      (node (ref "R200") (pin "1") (pinfunction "1_1") (pintype "passive"))
      (node (ref "U3") (pin "14") (pinfunction "SCL_14") (pintype "passive"))
    )
    (net (code "93") (name "MUX_SDA") (class "Default")
      (node (ref "J1") (pin "H37") (pinfunction "LA32_P_H37") (pintype "bidirectional"))
      (node (ref "R201") (pin "1") (pinfunction "1_1") (pintype "passive"))
      (node (ref "U3") (pin "15") (pinfunction "SDA_15") (pintype "passive"))
    )
    (net (code "94") (name "Net-(C501-Pad1)") (class "Default")
      (node (ref "C501") (pin "1") (pinfunction "1_1") (pintype "passive"))
      (node (ref "R506") (pin "1") (pinfunction "1_1") (pintype "passive"))
    )
    (net (code "95") (name "Net-(J1A-DP0_C2M_N)") (class "Default")
      (node (ref "J1") (pin "C3") (pinfunction "DP0_C2M_N_C3") (pintype "output"))
      (node (ref "PAD9") (pin "1") (pinfunction "P_1") (pintype "passive"))
    )
    (net (code "96") (name "Net-(J1A-DP0_C2M_P)") (class "Default")
      (node (ref "J1") (pin "C2") (pinfunction "DP0_C2M_P_C2") (pintype "output"))
      (node (ref "PAD8") (pin "1") (pinfunction "P_1") (pintype "passive"))
    )
    (net (code "97") (name "Net-(J1A-DP0_M2C_N)") (class "Default")
      (node (ref "J1") (pin "C7") (pinfunction "DP0_M2C_N_C7") (pintype "input"))
      (node (ref "PAD11") (pin "1") (pinfunction "P_1") (pintype "passive"))
    )
    (net (code "98") (name "Net-(J1A-DP0_M2C_P)") (class "Default")
      (node (ref "J1") (pin "C6") (pinfunction "DP0_M2C_P_C6") (pintype "input"))
      (node (ref "PAD10") (pin "1") (pinfunction "P_1") (pintype "passive"))
    )
    (net (code "99") (name "Net-(J1B-GBTCLK0_M2C_N)") (class "Default")
      (node (ref "J1") (pin "D5") (pinfunction "GBTCLK0_M2C_N_D5") (pintype "input"))
      (node (ref "PAD4") (pin "1") (pinfunction "P_1") (pintype "passive"))
    )
    (net (code "100") (name "Net-(J1B-GBTCLK0_M2C_P)") (class "Default")
      (node (ref "J1") (pin "D4") (pinfunction "GBTCLK0_M2C_P_D4") (pintype "input"))
      (node (ref "PAD3") (pin "1") (pinfunction "P_1") (pintype "passive"))
    )
    (net (code "101") (name "Net-(J1B-TCK)") (class "Default")
      (node (ref "J1") (pin "D29") (pinfunction "TCK_D29") (pintype "output"))
      (node (ref "PAD5") (pin "1") (pinfunction "P_1") (pintype "passive"))
    )
    (net (code "102") (name "Net-(J1B-TDI)") (class "Default")
      (node (ref "J1") (pin "D30") (pinfunction "TDI_D30") (pintype "output"))
      (node (ref "J1") (pin "D31") (pinfunction "TDO_D31") (pintype "input"))
    )
    (net (code "103") (name "Net-(J1B-TMS)") (class "Default")
      (node (ref "J1") (pin "D33") (pinfunction "TMS_D33") (pintype "output"))
      (node (ref "PAD6") (pin "1") (pinfunction "P_1") (pintype "passive"))
    )
    (net (code "104") (name "Net-(J1B-TRST_L)") (class "Default")
      (node (ref "J1") (pin "D34") (pinfunction "TRST_L_D34") (pintype "output"))
      (node (ref "PAD7") (pin "1") (pinfunction "P_1") (pintype "passive"))
    )
    (net (code "105") (name "Net-(J1D-CLK0_M2C_N)") (class "Default")
      (node (ref "J1") (pin "H5") (pinfunction "CLK0_M2C_N_H5") (pintype "bidirectional"))
      (node (ref "PAD2") (pin "1") (pinfunction "P_1") (pintype "passive"))
    )
    (net (code "106") (name "Net-(J1D-FREF_A_M2C)") (class "Default")
      (node (ref "J1") (pin "H1") (pinfunction "FREF_A_M2C_H1") (pintype "passive"))
      (node (ref "PAD1") (pin "1") (pinfunction "P_1") (pintype "passive"))
    )
    (net (code "107") (name "Net-(LED1-PadA)") (class "Default")
      (node (ref "LED1") (pin "A") (pinfunction "A_A") (pintype "passive"))
      (node (ref "R105") (pin "2") (pinfunction "2_2") (pintype "passive"))
    )
    (net (code "108") (name "Net-(U4-S0)") (class "Default")
      (node (ref "R212") (pin "1") (pinfunction "1_1") (pintype "passive"))
      (node (ref "U4") (pin "2") (pinfunction "S0_2") (pintype "input"))
    )
    (net (code "109") (name "Net-(U4-VCTR)") (class "Default")
      (node (ref "R211") (pin "1") (pinfunction "1_1") (pintype "passive"))
      (node (ref "U4") (pin "4") (pinfunction "VCTR_4") (pintype "input"))
    )
    (net (code "110") (name "Net-(U4-VDD)") (class "Default")
      (node (ref "C203") (pin "1") (pinfunction "1_1") (pintype "passive"))
      (node (ref "R211") (pin "2") (pinfunction "2_2") (pintype "passive"))
      (node (ref "R212") (pin "2") (pinfunction "2_2") (pintype "passive"))
      (node (ref "U$10") (pin "2") (pinfunction "2_2") (pintype "passive"))
      (node (ref "U4") (pin "3") (pinfunction "VDD_3") (pintype "power_in"))
    )
    (net (code "111") (name "Net-(U4-VDDOUT)") (class "Default")
      (node (ref "C201") (pin "1") (pinfunction "1_1") (pintype "passive"))
      (node (ref "C202") (pin "1") (pinfunction "1_1") (pintype "passive"))
      (node (ref "U$12") (pin "2") (pinfunction "2_2") (pintype "passive"))
      (node (ref "U4") (pin "6") (pinfunction "VDDOUT_2_6") (pintype "power_in"))
      (node (ref "U4") (pin "9") (pinfunction "VDDOUT_9") (pintype "power_in"))
    )
    (net (code "112") (name "Net-(U4-XIN{slash}CLK)") (class "Default")
      (node (ref "Q1") (pin "1") (pinfunction "1_1") (pintype "passive"))
      (node (ref "U4") (pin "1") (pinfunction "XIN/CLK_1") (pintype "input"))
    )
    (net (code "113") (name "Net-(U4-XOUT)") (class "Default")
      (node (ref "Q1") (pin "2") (pinfunction "2_2") (pintype "passive"))
      (node (ref "U4") (pin "16") (pinfunction "XOUT_16") (pintype "output"))
    )
    (net (code "114") (name "Net-(U4-Y4)") (class "Default")
      (node (ref "C209") (pin "1") (pinfunction "1_1") (pintype "passive"))
      (node (ref "U4") (pin "7") (pinfunction "Y4_7") (pintype "output"))
    )
    (net (code "115") (name "Net-(U4-Y5)") (class "Default")
      (node (ref "C210") (pin "1") (pinfunction "1_1") (pintype "passive"))
      (node (ref "U4") (pin "8") (pinfunction "Y5_8") (pintype "output"))
    )
    (net (code "116") (name "Net-(U5-NR{slash}FB)") (class "Default")
      (node (ref "C207") (pin "1") (pinfunction "1_1") (pintype "passive"))
      (node (ref "U5") (pin "4") (pinfunction "NR/FB_4") (pintype "bidirectional"))
    )
    (net (code "117") (name "Net-(U8-BOOT)") (class "Default")
      (node (ref "C503") (pin "1") (pinfunction "1_1") (pintype "passive"))
      (node (ref "U8") (pin "1") (pinfunction "BOOT_1") (pintype "output"))
    )
    (net (code "118") (name "Net-(U8-COMP)") (class "Default")
      (node (ref "C502") (pin "1") (pinfunction "1_1") (pintype "passive"))
      (node (ref "R506") (pin "2") (pinfunction "2_2") (pintype "passive"))
      (node (ref "U8") (pin "8") (pinfunction "COMP_8") (pintype "output"))
    )
    (net (code "119") (name "Net-(U8-EN)") (class "Default")
      (node (ref "R500") (pin "1") (pinfunction "1_1") (pintype "passive"))
      (node (ref "R501") (pin "2") (pinfunction "2_2") (pintype "passive"))
      (node (ref "U8") (pin "3") (pinfunction "EN_3") (pintype "input"))
    )
    (net (code "120") (name "Net-(U8-PH)") (class "Default")
      (node (ref "C503") (pin "2") (pinfunction "2_2") (pintype "passive"))
      (node (ref "D1") (pin "C") (pinfunction "C_C") (pintype "passive"))
      (node (ref "U$24") (pin "1") (pinfunction "1_1") (pintype "passive"))
      (node (ref "U8") (pin "10") (pinfunction "PH_10") (pintype "input"))
    )
    (net (code "121") (name "Net-(U8-RT{slash}CLK)") (class "Default")
      (node (ref "R502") (pin "2") (pinfunction "2_2") (pintype "passive"))
      (node (ref "U8") (pin "5") (pinfunction "RT/CLK_5") (pintype "input"))
    )
    (net (code "122") (name "Net-(U8-SS{slash}TR)") (class "Default")
      (node (ref "C500") (pin "1") (pinfunction "1_1") (pintype "passive"))
      (node (ref "U8") (pin "4") (pinfunction "SS/TR_4") (pintype "input"))
    )
    (net (code "123") (name "Net-(U8-VIN)") (class "Default")
      (node (ref "C507") (pin "1") (pinfunction "1_1") (pintype "passive"))
      (node (ref "C510") (pin "1") (pinfunction "1_1") (pintype "passive"))
      (node (ref "R500") (pin "2") (pinfunction "2_2") (pintype "passive"))
      (node (ref "U$23") (pin "2") (pinfunction "2_2") (pintype "passive"))
      (node (ref "U8") (pin "2") (pinfunction "VIN_2") (pintype "input"))
    )
    (net (code "124") (name "Net-(U8-VSENSE)") (class "Default")
      (node (ref "R503") (pin "1") (pinfunction "1_1") (pintype "passive"))
      (node (ref "R504") (pin "2") (pinfunction "2_2") (pintype "passive"))
      (node (ref "U8") (pin "7") (pinfunction "VSENSE_7") (pintype "input"))
    )
    (net (code "125") (name "PG_C2M") (class "Default")
      (node (ref "J1") (pin "D1") (pinfunction "PG_C2M_D1") (pintype "output"))
      (node (ref "R105") (pin "1") (pinfunction "1_1") (pintype "passive"))
      (node (ref "R106") (pin "2") (pinfunction "2_2") (pintype "passive"))
      (node (ref "U2") (pin "2") (pinfunction "A_2") (pintype "input"))
    )
    (net (code "126") (name "REG_1P8V") (class "Default")
      (node (ref "C208") (pin "1") (pinfunction "1_1") (pintype "passive"))
      (node (ref "U$10") (pin "1") (pinfunction "1_1") (pintype "passive"))
      (node (ref "U5") (pin "5") (pinfunction "OUT_5") (pintype "output"))
    )
    (net (code "127") (name "REG_5P0V") (class "Default")
      (node (ref "C508") (pin "1") (pinfunction "1_1") (pintype "passive"))
      (node (ref "R209") (pin "2") (pinfunction "2_2") (pintype "passive"))
      (node (ref "R210") (pin "2") (pinfunction "2_2") (pintype "passive"))
      (node (ref "R503") (pin "2") (pinfunction "2_2") (pintype "passive"))
      (node (ref "U$24") (pin "2") (pinfunction "2_2") (pintype "passive"))
    )
    (net (code "128") (name "TMDS_PLL_SCL") (class "Default")
      (node (ref "R208") (pin "1") (pinfunction "1_1") (pintype "passive"))
      (node (ref "U3") (pin "10") (pinfunction "SC2_10") (pintype "passive"))
      (node (ref "U4") (pin "14") (pinfunction "S2/SCL_14") (pintype "input"))
    )
    (net (code "129") (name "TMDS_PLL_SDA") (class "Default")
      (node (ref "R207") (pin "1") (pinfunction "1_1") (pintype "passive"))
      (node (ref "U3") (pin "9") (pinfunction "SD2_9") (pintype "passive"))
      (node (ref "U4") (pin "15") (pinfunction "S1/SDA_15") (pintype "bidirectional"))
    )
    (net (code "130") (name "VADJ") (class "Default")
      (node (ref "C106") (pin "1") (pinfunction "1_1") (pintype "passive"))
      (node (ref "C107") (pin "1") (pinfunction "1_1") (pintype "passive"))
      (node (ref "C200") (pin "1") (pinfunction "1_1") (pintype "passive"))
      (node (ref "C307") (pin "1") (pinfunction "1_1") (pintype "passive"))
      (node (ref "C308") (pin "1") (pinfunction "1_1") (pintype "passive"))
      (node (ref "C311") (pin "1") (pinfunction "1_1") (pintype "passive"))
      (node (ref "C312") (pin "1") (pinfunction "1_1") (pintype "passive"))
      (node (ref "C315") (pin "1") (pinfunction "1_1") (pintype "passive"))
      (node (ref "C316") (pin "1") (pinfunction "1_1") (pintype "passive"))
      (node (ref "J1") (pin "G39") (pinfunction "VADJ_G39") (pintype "passive"))
      (node (ref "J1") (pin "H40") (pinfunction "VADJ_H40") (pintype "passive"))
      (node (ref "R200") (pin "2") (pinfunction "2_2") (pintype "passive"))
      (node (ref "R201") (pin "2") (pinfunction "2_2") (pintype "passive"))
      (node (ref "R204") (pin "2") (pinfunction "2_2") (pintype "passive"))
      (node (ref "U$12") (pin "1") (pinfunction "1_1") (pintype "passive"))
      (node (ref "U1") (pin "18") (pinfunction "VCCB_18") (pintype "power_in"))
      (node (ref "U1") (pin "7") (pinfunction "VCCB_2_7") (pintype "power_in"))
      (node (ref "U3") (pin "16") (pinfunction "VCC_16") (pintype "power_in"))
      (node (ref "U6") (pin "18") (pinfunction "VCCB_18") (pintype "power_in"))
      (node (ref "U6") (pin "7") (pinfunction "VCCB_2_7") (pintype "power_in"))
      (node (ref "U7") (pin "18") (pinfunction "VCCB_18") (pintype "power_in"))
      (node (ref "U7") (pin "7") (pinfunction "VCCB_2_7") (pintype "power_in"))
    )
    (net (code "131") (name "VIDEO_CLK_S6") (class "Default")
      (node (ref "J1") (pin "G3") (pinfunction "CLK1_M2C_N_G3") (pintype "bidirectional"))
    )
    (net (code "132") (name "VIDEO_CLK_V6") (class "Default")
      (node (ref "J1") (pin "G6") (pinfunction "LA00_P_CC_G6") (pintype "bidirectional"))
    )
    (net (code "133") (name "unconnected-(C209-Pad2)") (class "Default")
      (node (ref "C209") (pin "2") (pinfunction "2_2") (pintype "passive"))
    )
    (net (code "134") (name "unconnected-(C210-Pad2)") (class "Default")
      (node (ref "C210") (pin "2") (pinfunction "2_2") (pintype "passive"))
    )
    (net (code "135") (name "unconnected-(U1-1A1-Pad47)") (class "Default")
      (node (ref "U1") (pin "47") (pinfunction "1A1_47") (pintype "bidirectional"))
    )
    (net (code "136") (name "unconnected-(U1-1A2-Pad46)") (class "Default")
      (node (ref "U1") (pin "46") (pinfunction "1A2_46") (pintype "bidirectional"))
    )
    (net (code "137") (name "unconnected-(U1-1A3-Pad44)") (class "Default")
      (node (ref "U1") (pin "44") (pinfunction "1A3_44") (pintype "bidirectional"))
    )
    (net (code "138") (name "unconnected-(U1-1A4-Pad43)") (class "Default")
      (node (ref "U1") (pin "43") (pinfunction "1A4_43") (pintype "bidirectional"))
    )
    (net (code "139") (name "unconnected-(U1-1A5-Pad41)") (class "Default")
      (node (ref "U1") (pin "41") (pinfunction "1A5_41") (pintype "bidirectional"))
    )
    (net (code "140") (name "unconnected-(U1-1A6-Pad40)") (class "Default")
      (node (ref "U1") (pin "40") (pinfunction "1A6_40") (pintype "bidirectional"))
    )
    (net (code "141") (name "unconnected-(U1-1A7-Pad38)") (class "Default")
      (node (ref "U1") (pin "38") (pinfunction "1A7_38") (pintype "bidirectional"))
    )
    (net (code "142") (name "unconnected-(U1-1A8-Pad37)") (class "Default")
      (node (ref "U1") (pin "37") (pinfunction "1A8_37") (pintype "bidirectional"))
    )
    (net (code "143") (name "unconnected-(U1-1B3-Pad5)") (class "Default")
      (node (ref "U1") (pin "5") (pinfunction "1B3_5") (pintype "bidirectional"))
    )
    (net (code "144") (name "unconnected-(U1-1B4-Pad6)") (class "Default")
      (node (ref "U1") (pin "6") (pinfunction "1B4_6") (pintype "bidirectional"))
    )
    (net (code "145") (name "unconnected-(U1-1B5-Pad8)") (class "Default")
      (node (ref "U1") (pin "8") (pinfunction "1B5_8") (pintype "bidirectional"))
    )
    (net (code "146") (name "unconnected-(U1-1B6-Pad9)") (class "Default")
      (node (ref "U1") (pin "9") (pinfunction "1B6_9") (pintype "bidirectional"))
    )
    (net (code "147") (name "unconnected-(U1-2A1-Pad36)") (class "Default")
      (node (ref "U1") (pin "36") (pinfunction "2A1_36") (pintype "bidirectional"))
    )
    (net (code "148") (name "unconnected-(U1-2A2-Pad35)") (class "Default")
      (node (ref "U1") (pin "35") (pinfunction "2A2_35") (pintype "bidirectional"))
    )
    (net (code "149") (name "unconnected-(U1-2A3-Pad33)") (class "Default")
      (node (ref "U1") (pin "33") (pinfunction "2A3_33") (pintype "bidirectional"))
    )
    (net (code "150") (name "unconnected-(U1-2A4-Pad32)") (class "Default")
      (node (ref "U1") (pin "32") (pinfunction "2A4_32") (pintype "bidirectional"))
    )
    (net (code "151") (name "unconnected-(U1-2A5-Pad30)") (class "Default")
      (node (ref "U1") (pin "30") (pinfunction "2A5_30") (pintype "bidirectional"))
    )
    (net (code "152") (name "unconnected-(U1-2A6-Pad29)") (class "Default")
      (node (ref "U1") (pin "29") (pinfunction "2A6_29") (pintype "bidirectional"))
    )
    (net (code "153") (name "unconnected-(U1-2A7-Pad27)") (class "Default")
      (node (ref "U1") (pin "27") (pinfunction "2A7_27") (pintype "bidirectional"))
    )
    (net (code "154") (name "unconnected-(U1-2A8-Pad26)") (class "Default")
      (node (ref "U1") (pin "26") (pinfunction "2A8_26") (pintype "bidirectional"))
    )
    (net (code "155") (name "unconnected-(U2-NC-Pad1)") (class "Default")
      (node (ref "U2") (pin "1") (pinfunction "NC_1") (pintype "passive"))
    )
    (net (code "156") (name "unconnected-(U4-Y1-Pad13)") (class "Default")
      (node (ref "U4") (pin "13") (pinfunction "Y1_13") (pintype "output"))
    )
    (net (code "157") (name "unconnected-(U4-Y2-Pad11)") (class "Default")
      (node (ref "U4") (pin "11") (pinfunction "Y2_11") (pintype "output"))
    )
    (net (code "158") (name "unconnected-(U4-Y3-Pad10)") (class "Default")
      (node (ref "U4") (pin "10") (pinfunction "Y3_10") (pintype "output"))
    )
    (net (code "159") (name "unconnected-(U6-1A1-Pad47)") (class "Default")
      (node (ref "U6") (pin "47") (pinfunction "1A1_47") (pintype "bidirectional"))
    )
    (net (code "160") (name "unconnected-(U6-1A2-Pad46)") (class "Default")
      (node (ref "U6") (pin "46") (pinfunction "1A2_46") (pintype "bidirectional"))
    )
    (net (code "161") (name "unconnected-(U6-1A3-Pad44)") (class "Default")
      (node (ref "U6") (pin "44") (pinfunction "1A3_44") (pintype "bidirectional"))
    )
    (net (code "162") (name "unconnected-(U6-1A4-Pad43)") (class "Default")
      (node (ref "U6") (pin "43") (pinfunction "1A4_43") (pintype "bidirectional"))
    )
    (net (code "163") (name "unconnected-(U6-1A5-Pad41)") (class "Default")
      (node (ref "U6") (pin "41") (pinfunction "1A5_41") (pintype "bidirectional"))
    )
    (net (code "164") (name "unconnected-(U6-1A6-Pad40)") (class "Default")
      (node (ref "U6") (pin "40") (pinfunction "1A6_40") (pintype "bidirectional"))
    )
    (net (code "165") (name "unconnected-(U6-1A7-Pad38)") (class "Default")
      (node (ref "U6") (pin "38") (pinfunction "1A7_38") (pintype "bidirectional"))
    )
    (net (code "166") (name "unconnected-(U6-1A8-Pad37)") (class "Default")
      (node (ref "U6") (pin "37") (pinfunction "1A8_37") (pintype "bidirectional"))
    )
    (net (code "167") (name "unconnected-(U6-2A1-Pad36)") (class "Default")
      (node (ref "U6") (pin "36") (pinfunction "2A1_36") (pintype "bidirectional"))
    )
    (net (code "168") (name "unconnected-(U6-2A2-Pad35)") (class "Default")
      (node (ref "U6") (pin "35") (pinfunction "2A2_35") (pintype "bidirectional"))
    )
    (net (code "169") (name "unconnected-(U6-2A3-Pad33)") (class "Default")
      (node (ref "U6") (pin "33") (pinfunction "2A3_33") (pintype "bidirectional"))
    )
    (net (code "170") (name "unconnected-(U6-2A4-Pad32)") (class "Default")
      (node (ref "U6") (pin "32") (pinfunction "2A4_32") (pintype "bidirectional"))
    )
    (net (code "171") (name "unconnected-(U6-2A5-Pad30)") (class "Default")
      (node (ref "U6") (pin "30") (pinfunction "2A5_30") (pintype "bidirectional"))
    )
    (net (code "172") (name "unconnected-(U6-2A6-Pad29)") (class "Default")
      (node (ref "U6") (pin "29") (pinfunction "2A6_29") (pintype "bidirectional"))
    )
    (net (code "173") (name "unconnected-(U6-2A7-Pad27)") (class "Default")
      (node (ref "U6") (pin "27") (pinfunction "2A7_27") (pintype "bidirectional"))
    )
    (net (code "174") (name "unconnected-(U6-2A8-Pad26)") (class "Default")
      (node (ref "U6") (pin "26") (pinfunction "2A8_26") (pintype "bidirectional"))
    )
    (net (code "175") (name "unconnected-(U7-1A1-Pad47)") (class "Default")
      (node (ref "U7") (pin "47") (pinfunction "1A1_47") (pintype "bidirectional"))
    )
    (net (code "176") (name "unconnected-(U7-1A2-Pad46)") (class "Default")
      (node (ref "U7") (pin "46") (pinfunction "1A2_46") (pintype "bidirectional"))
    )
    (net (code "177") (name "unconnected-(U7-1A3-Pad44)") (class "Default")
      (node (ref "U7") (pin "44") (pinfunction "1A3_44") (pintype "bidirectional"))
    )
    (net (code "178") (name "unconnected-(U7-1A4-Pad43)") (class "Default")
      (node (ref "U7") (pin "43") (pinfunction "1A4_43") (pintype "bidirectional"))
    )
    (net (code "179") (name "unconnected-(U7-1A5-Pad41)") (class "Default")
      (node (ref "U7") (pin "41") (pinfunction "1A5_41") (pintype "bidirectional"))
    )
    (net (code "180") (name "unconnected-(U7-1A6-Pad40)") (class "Default")
      (node (ref "U7") (pin "40") (pinfunction "1A6_40") (pintype "bidirectional"))
    )
    (net (code "181") (name "unconnected-(U7-1A7-Pad38)") (class "Default")
      (node (ref "U7") (pin "38") (pinfunction "1A7_38") (pintype "bidirectional"))
    )
    (net (code "182") (name "unconnected-(U7-1A8-Pad37)") (class "Default")
      (node (ref "U7") (pin "37") (pinfunction "1A8_37") (pintype "bidirectional"))
    )
    (net (code "183") (name "unconnected-(U7-2A1-Pad36)") (class "Default")
      (node (ref "U7") (pin "36") (pinfunction "2A1_36") (pintype "bidirectional"))
    )
    (net (code "184") (name "unconnected-(U7-2A2-Pad35)") (class "Default")
      (node (ref "U7") (pin "35") (pinfunction "2A2_35") (pintype "bidirectional"))
    )
    (net (code "185") (name "unconnected-(U7-2A3-Pad33)") (class "Default")
      (node (ref "U7") (pin "33") (pinfunction "2A3_33") (pintype "bidirectional"))
    )
    (net (code "186") (name "unconnected-(U7-2A4-Pad32)") (class "Default")
      (node (ref "U7") (pin "32") (pinfunction "2A4_32") (pintype "bidirectional"))
    )
    (net (code "187") (name "unconnected-(U7-2A5-Pad30)") (class "Default")
      (node (ref "U7") (pin "30") (pinfunction "2A5_30") (pintype "bidirectional"))
    )
    (net (code "188") (name "unconnected-(U7-2A6-Pad29)") (class "Default")
      (node (ref "U7") (pin "29") (pinfunction "2A6_29") (pintype "bidirectional"))
    )
    (net (code "189") (name "unconnected-(U7-2A7-Pad27)") (class "Default")
      (node (ref "U7") (pin "27") (pinfunction "2A7_27") (pintype "bidirectional"))
    )
    (net (code "190") (name "unconnected-(U7-2A8-Pad26)") (class "Default")
      (node (ref "U7") (pin "26") (pinfunction "2A8_26") (pintype "bidirectional"))
    )
    (net (code "191") (name "unconnected-(U8-PWRGD-Pad6)") (class "Default")
      (node (ref "U8") (pin "6") (pinfunction "PWRGD_6") (pintype "output"))
    )
  )
)
